# Titan_v1p6.net
KiCad netlist of a schematic drawn in EAGLE
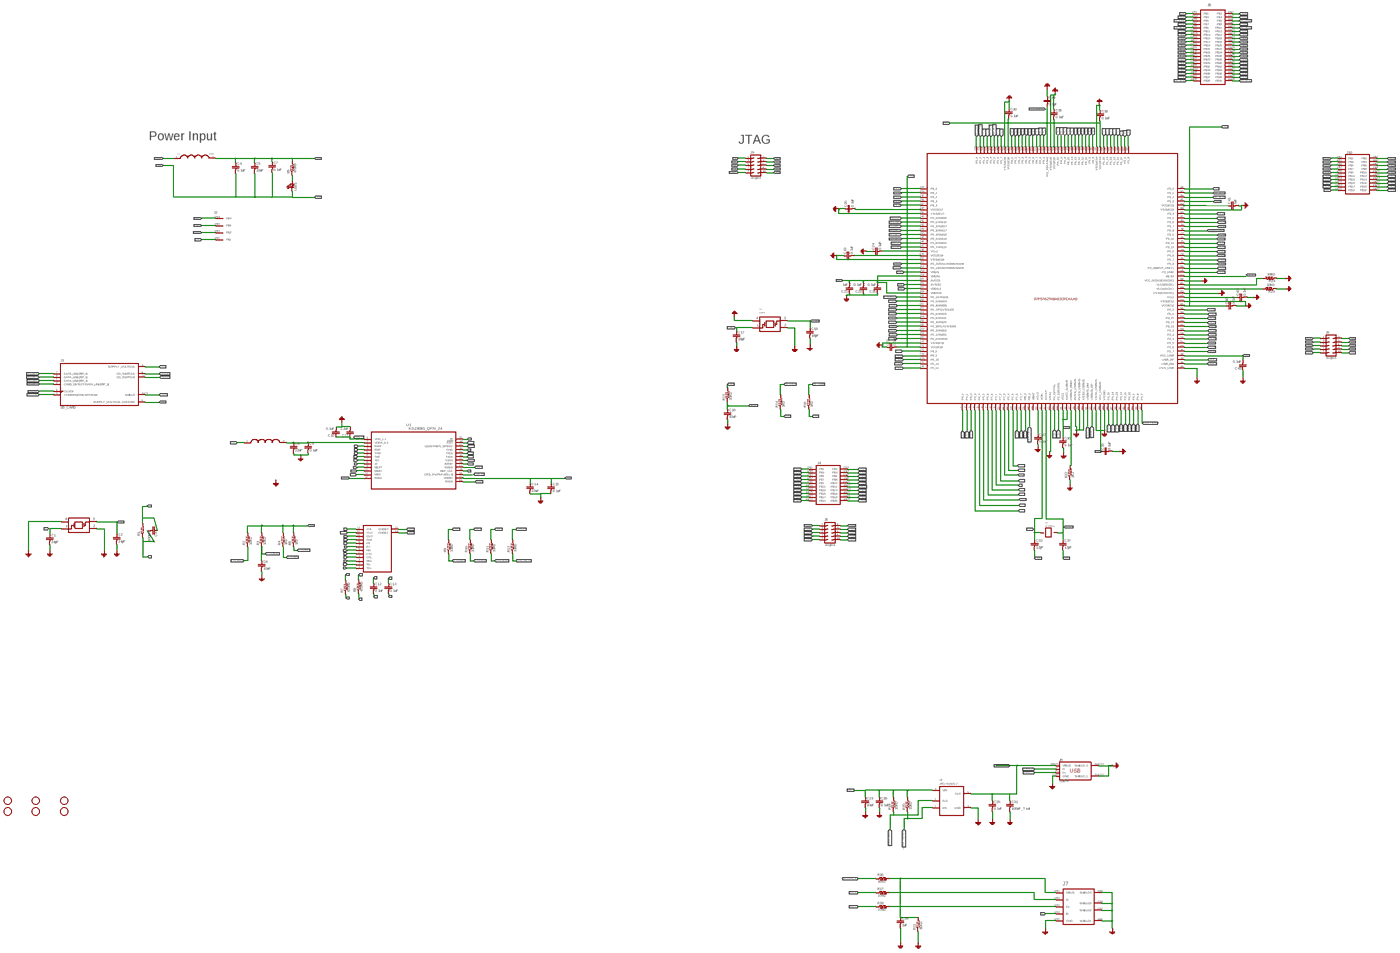
[diagram p0: schematic, sheet 1, overview]
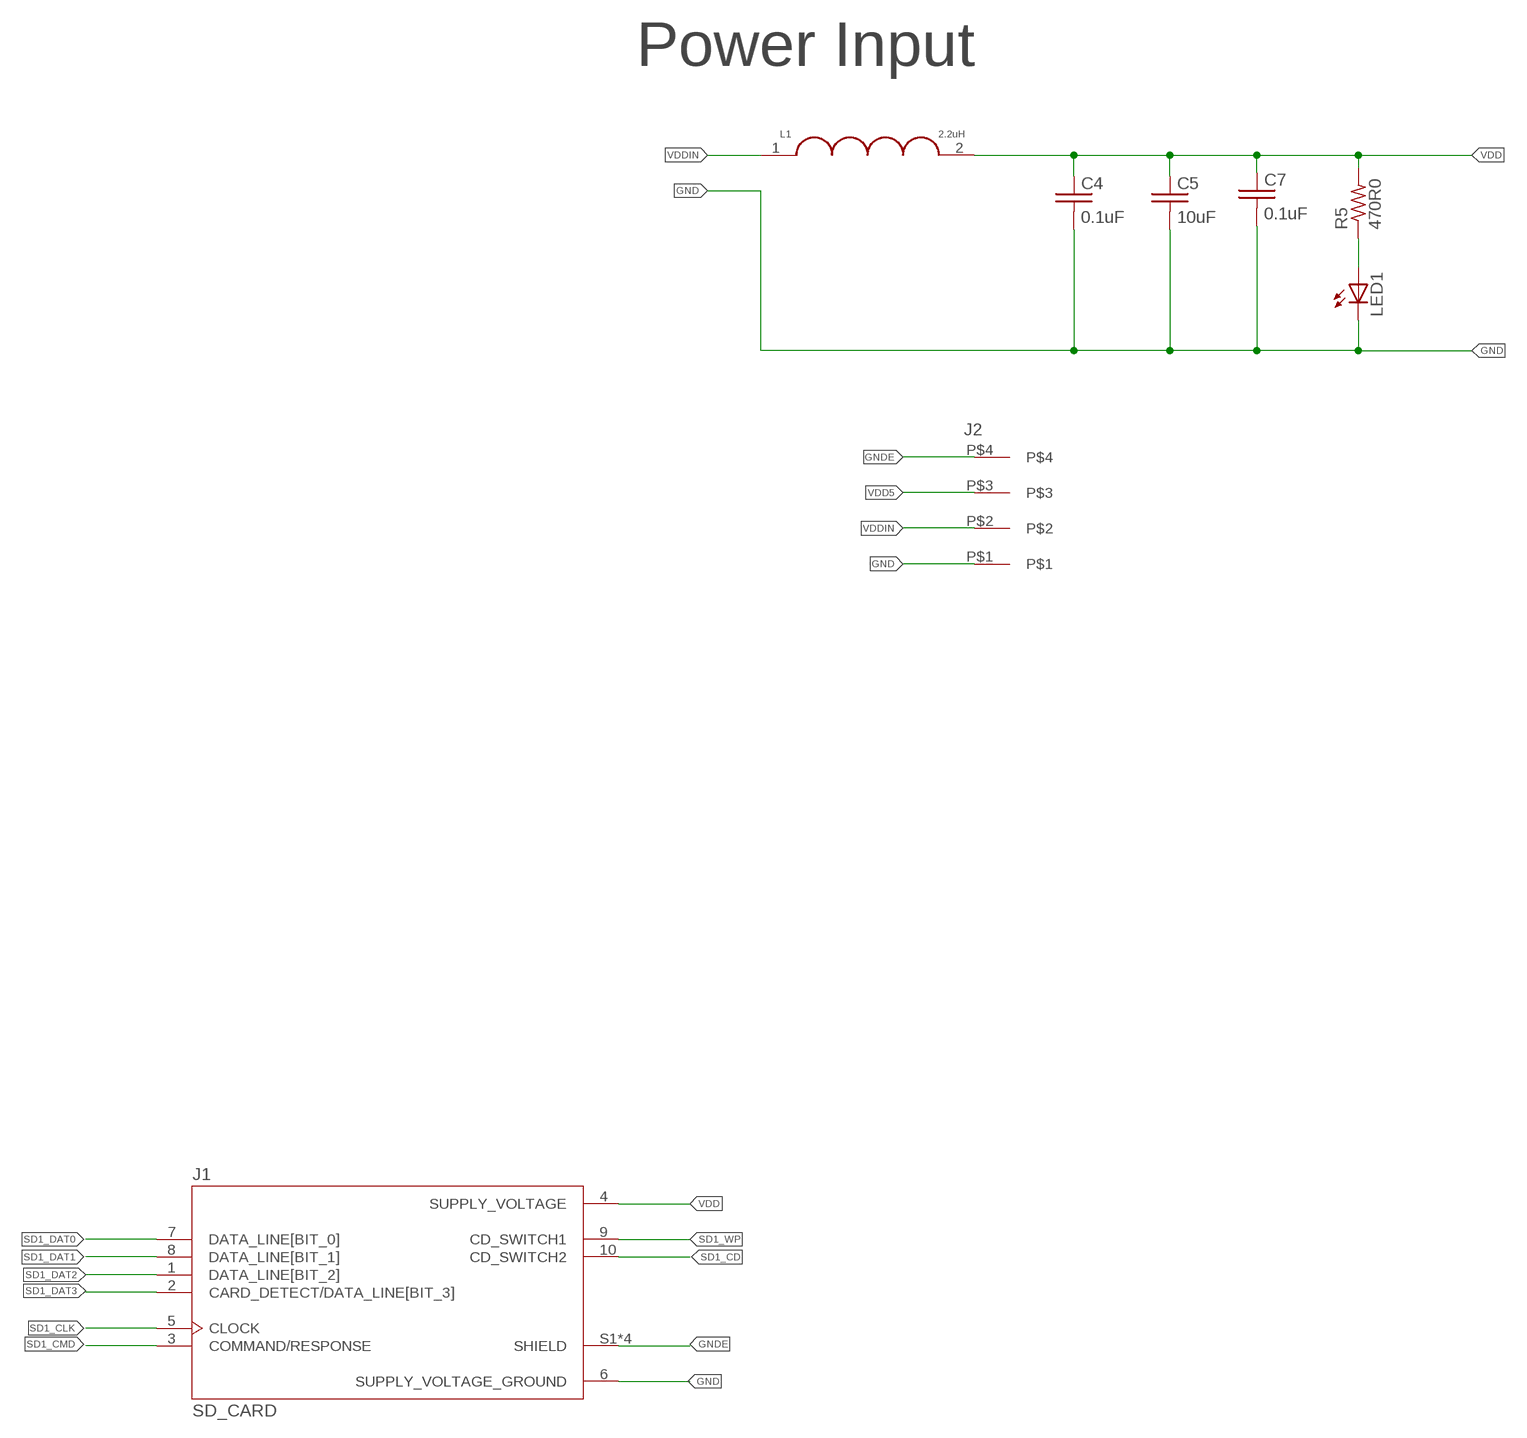
[diagram p1: schematic, sheet 1, part 1 of 5]
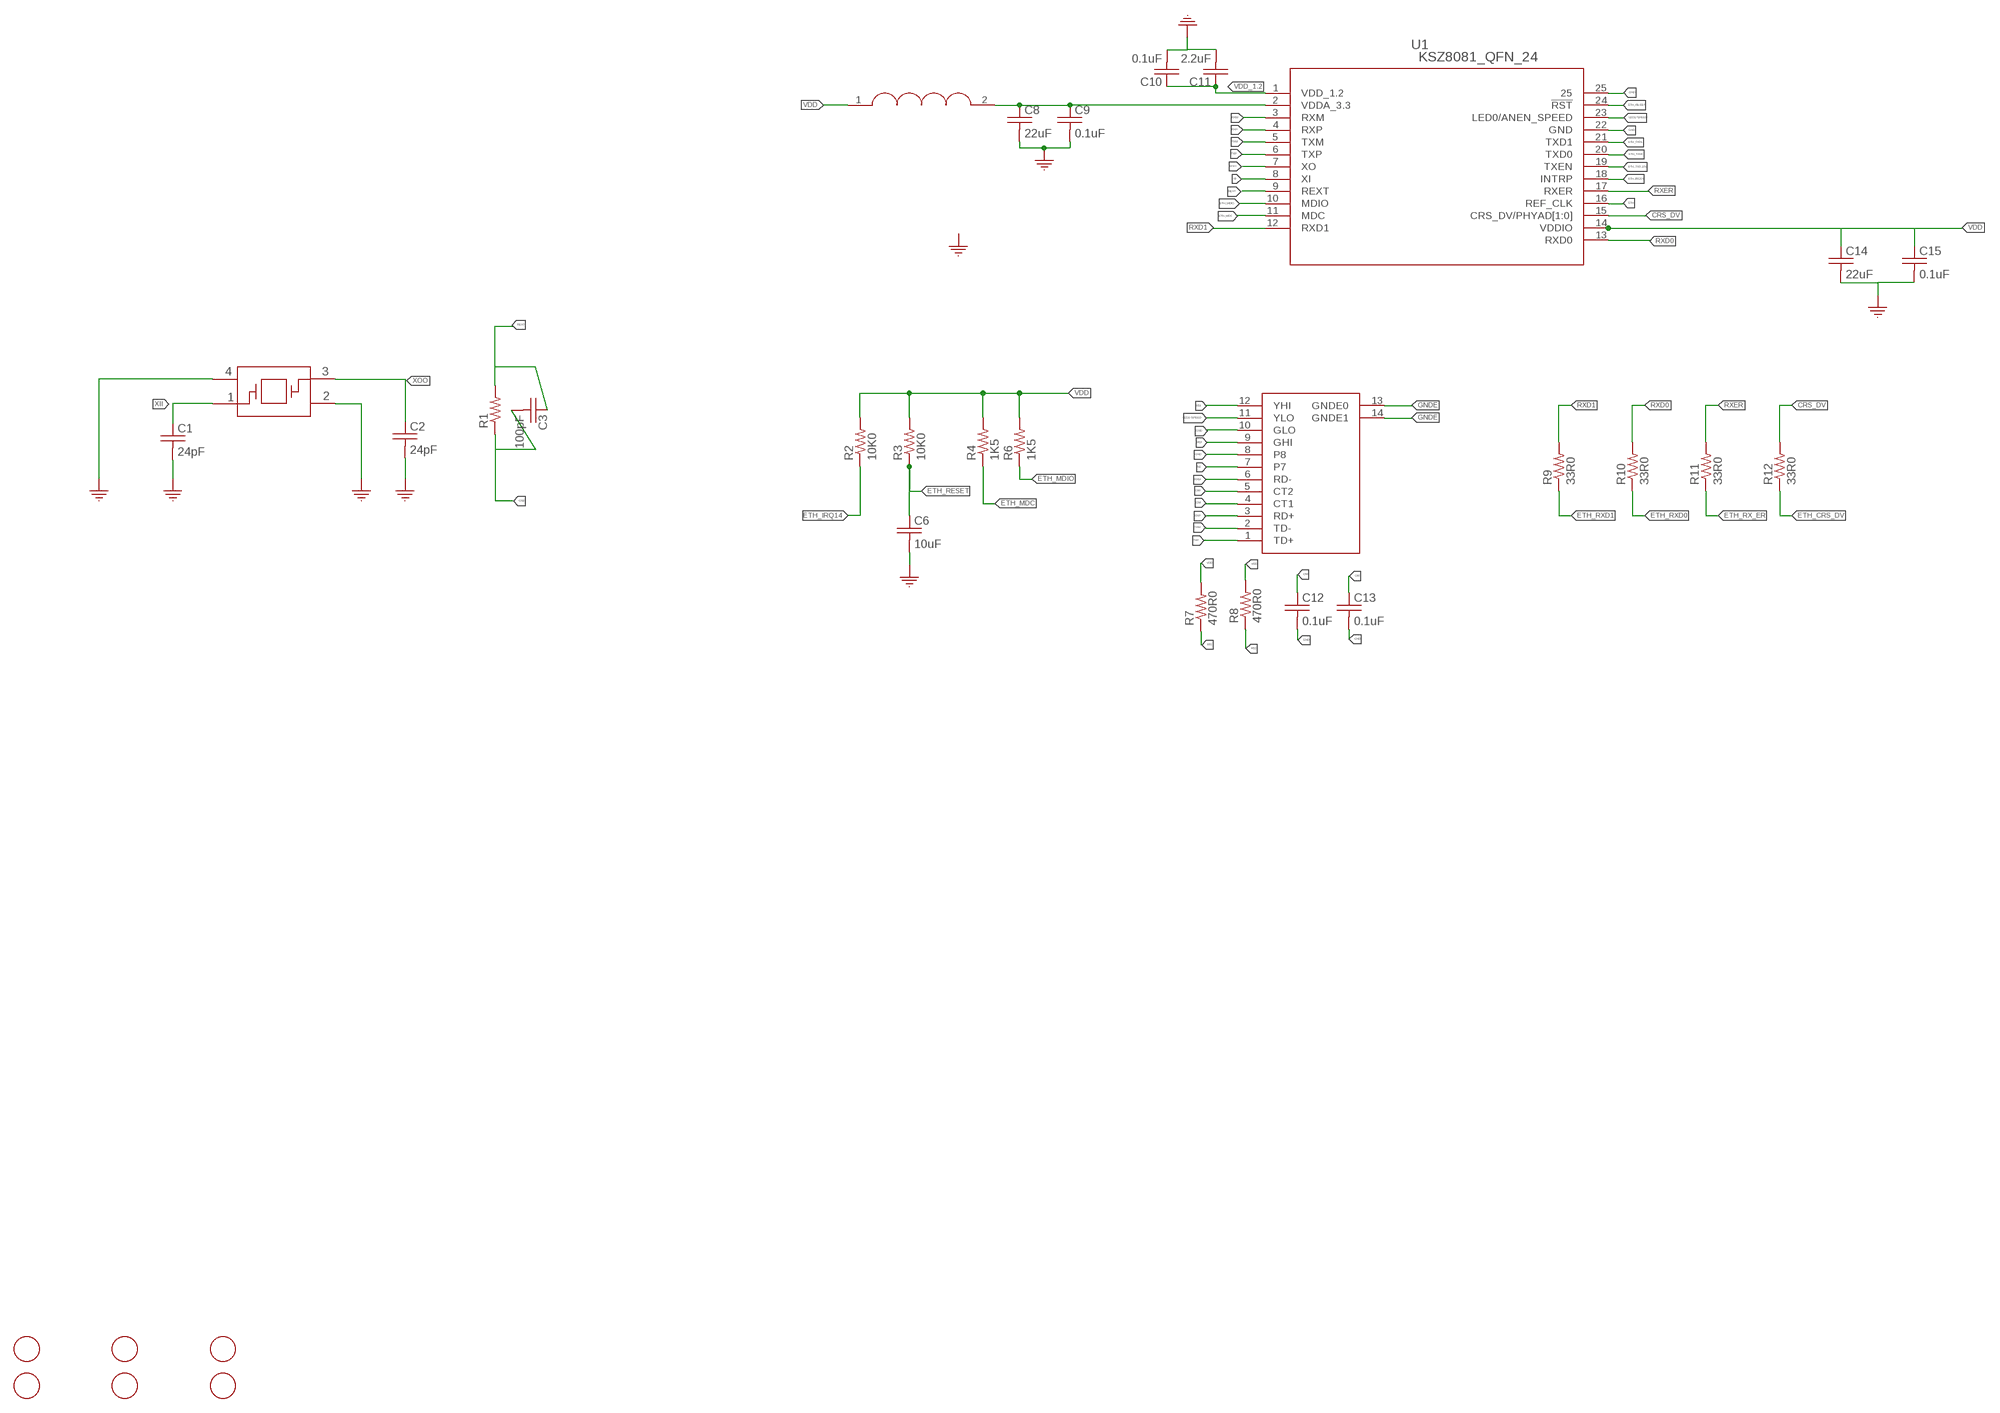
[diagram p2: schematic, sheet 1, part 2 of 5]
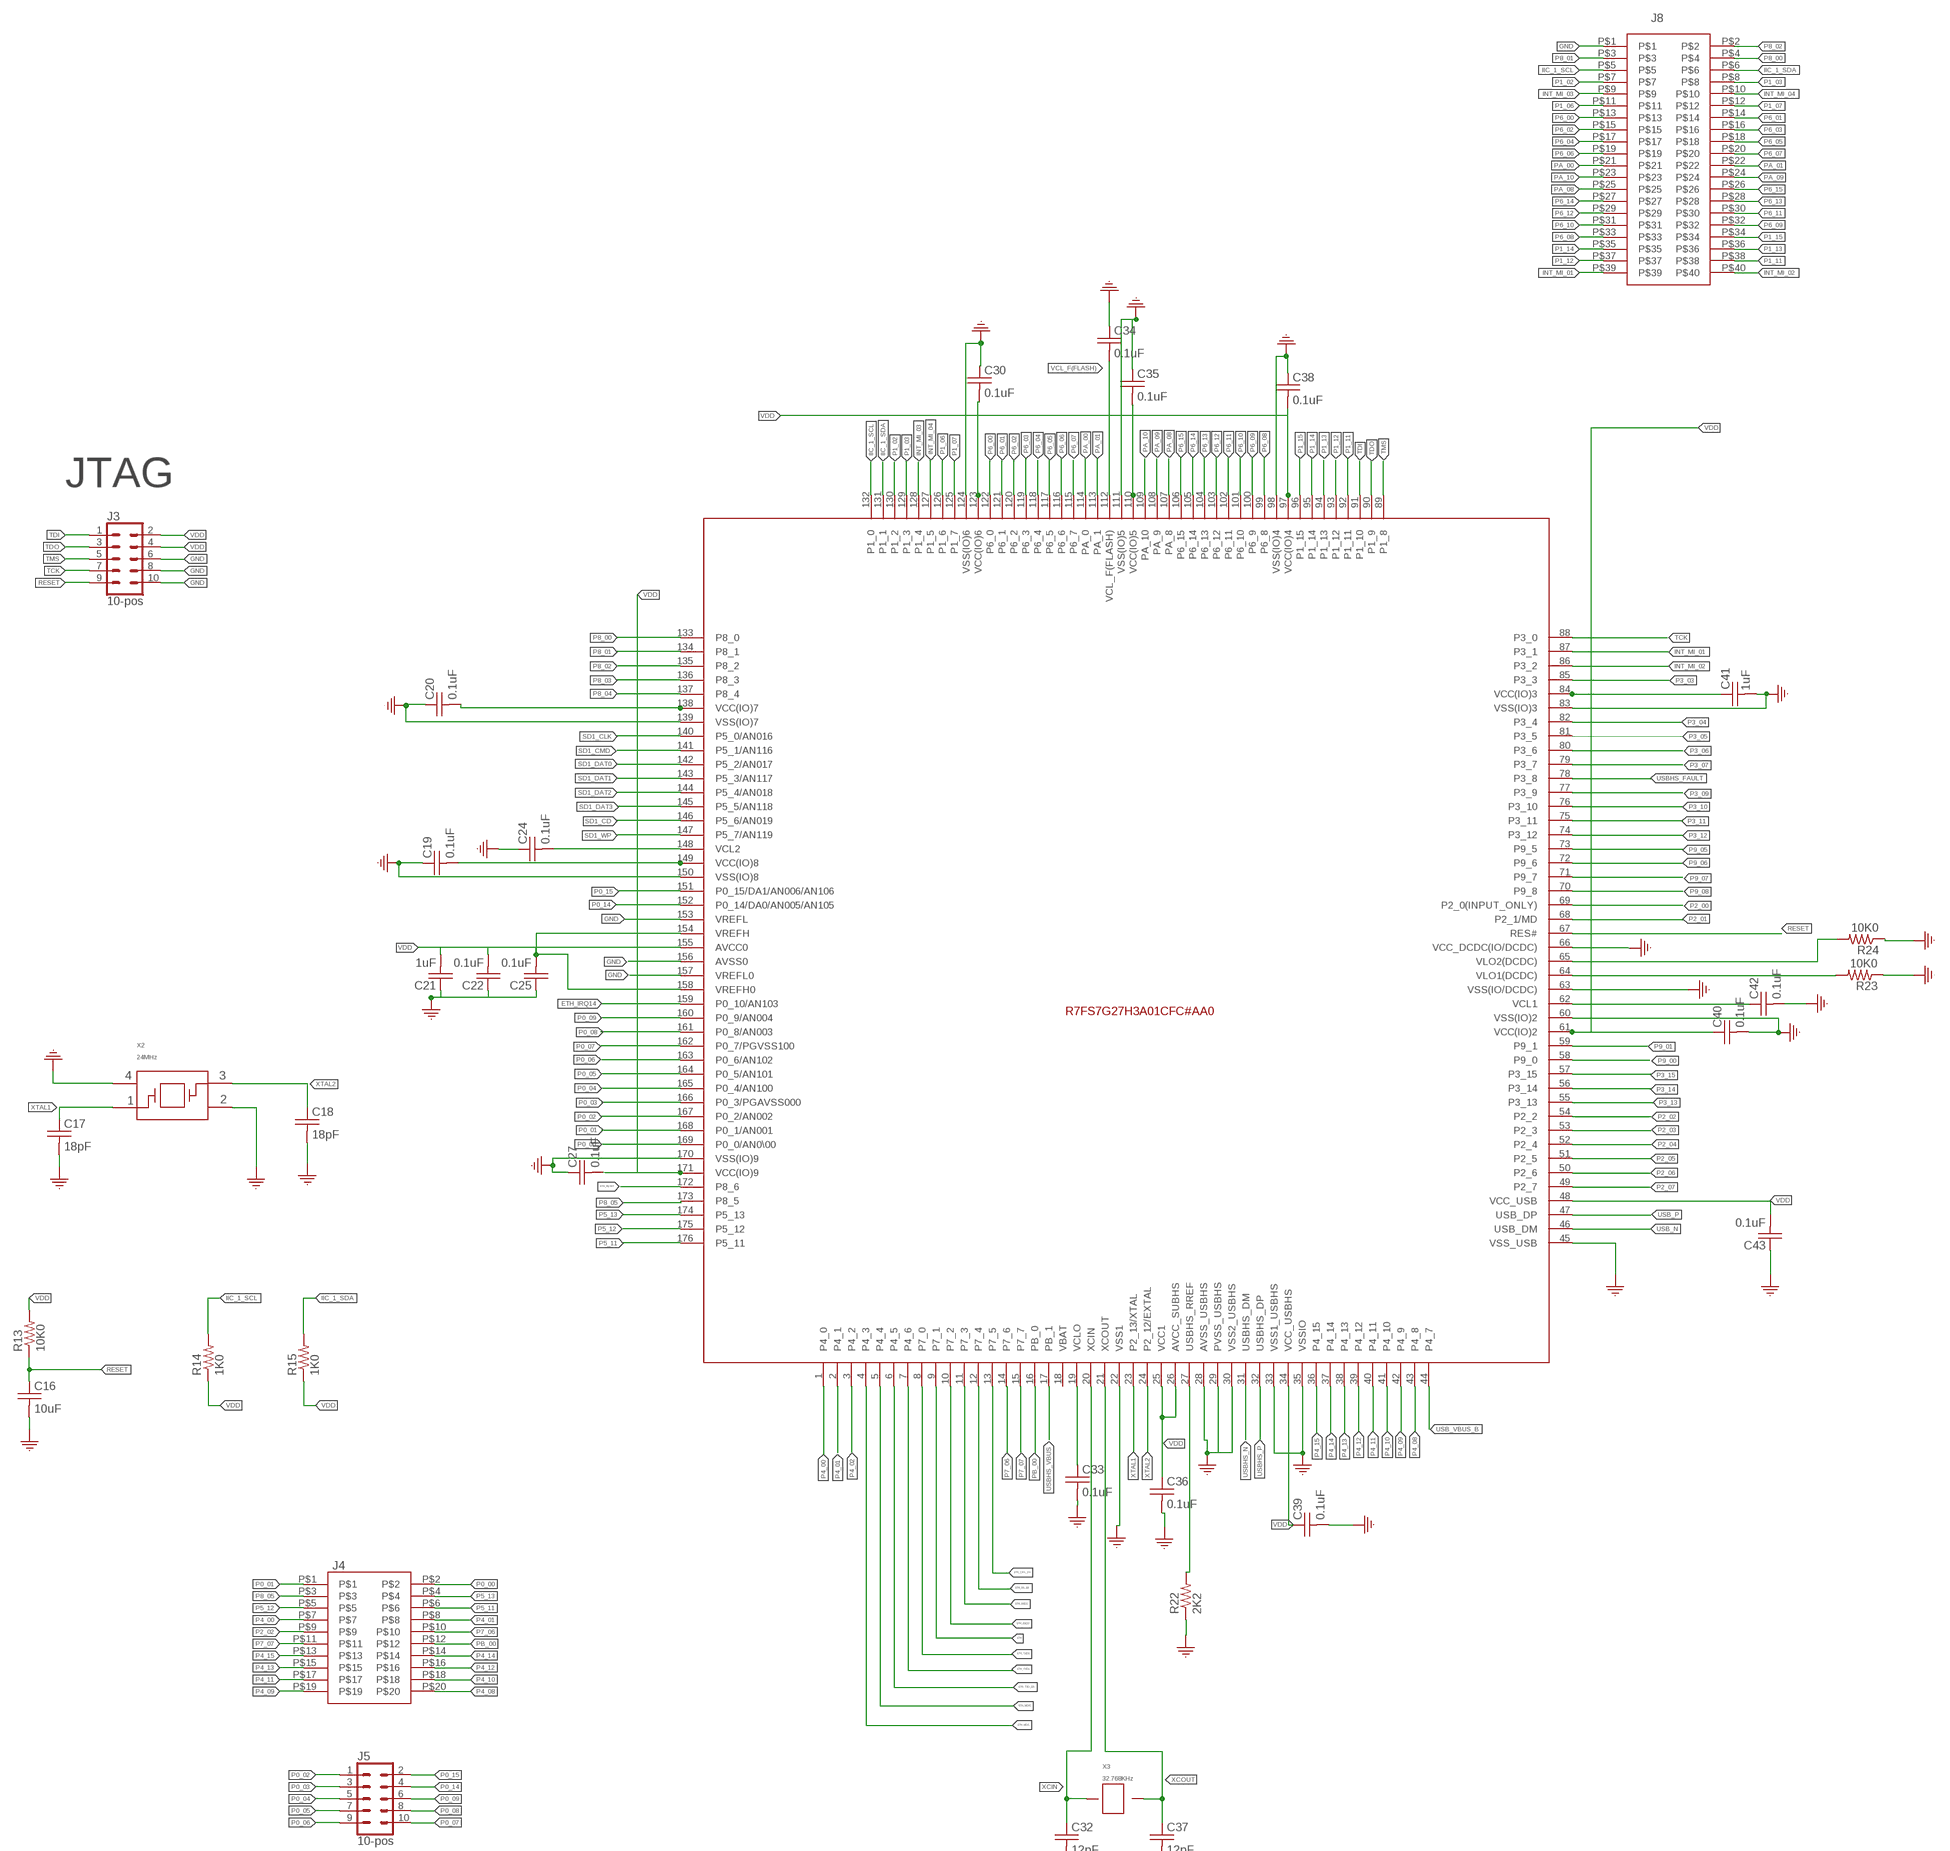
[diagram p3: schematic, sheet 1, part 3 of 5]
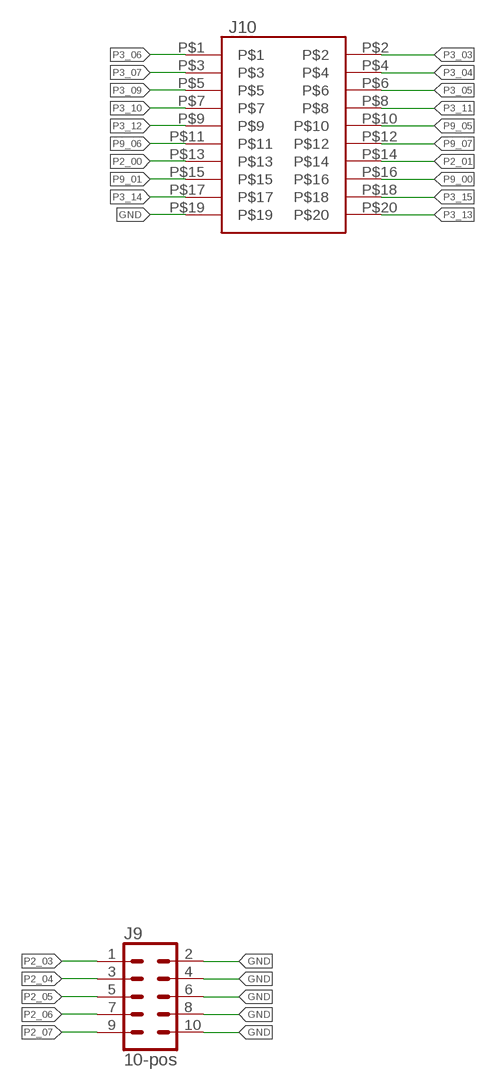
[diagram p4: schematic, sheet 1, part 4 of 5]
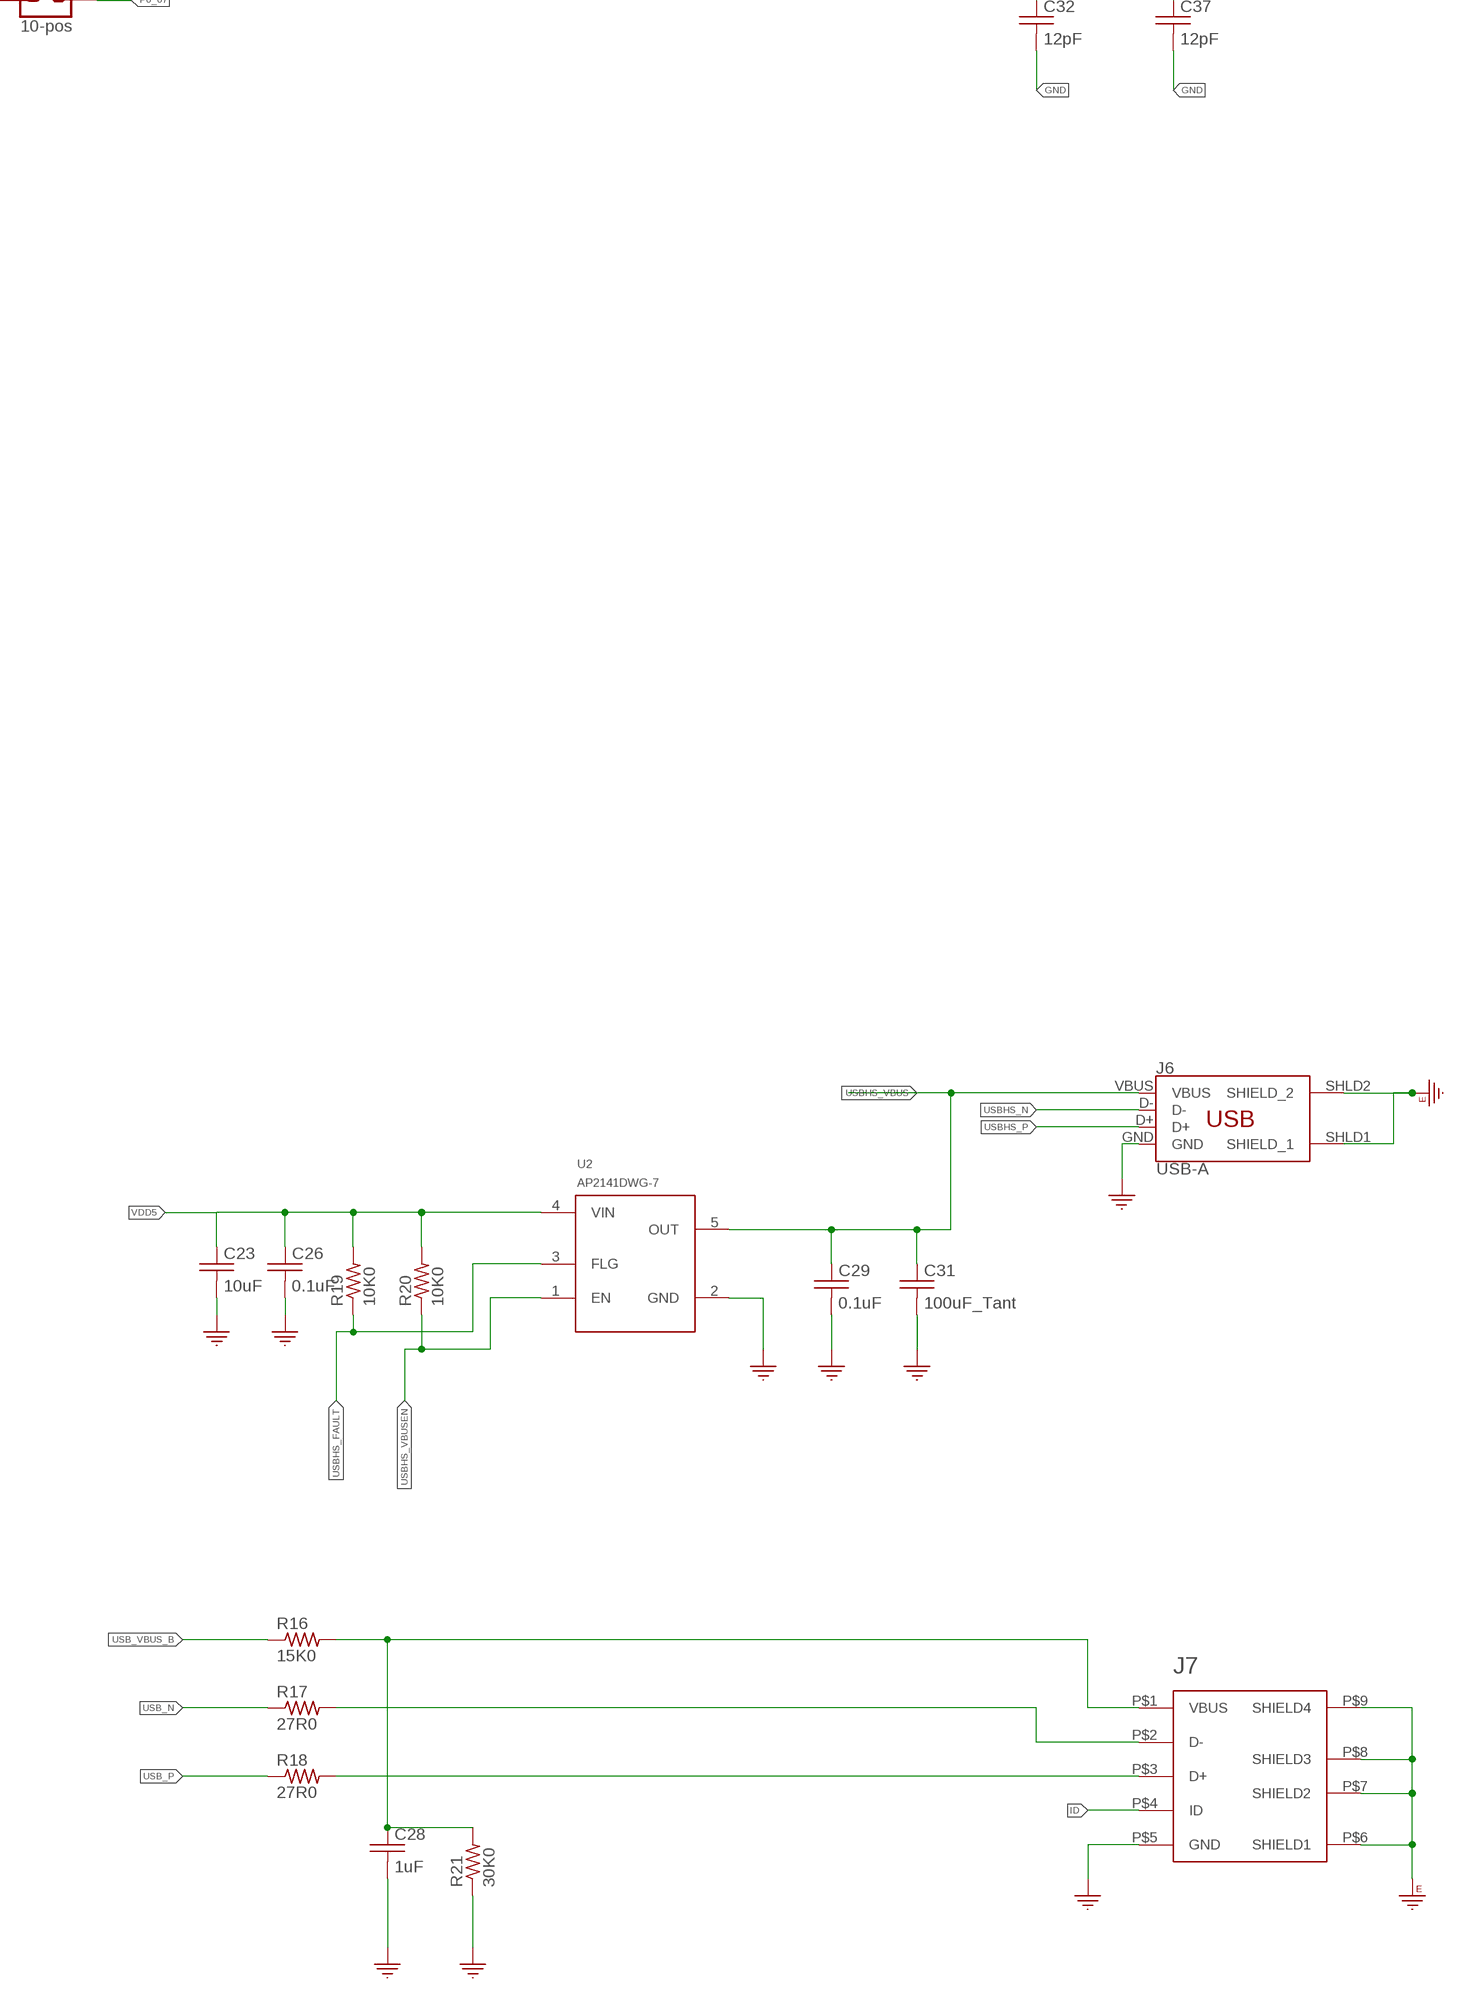
[diagram p5: schematic, sheet 1, part 5 of 5]

(export (version "E")
  (design (tool "Eeschema 10.0.6"))
  (components
    (comp (ref "AFID1")
      (value "FIDUCIAL_1MM")
      (footprint "eagle-import:FIDUCIAL_1MM")
      (libsource (lib "eagle-import") (part "FIDUCIAL_1MM"))
    )
    (comp (ref "AFID2")
      (value "FIDUCIAL_1MM")
      (footprint "eagle-import:FIDUCIAL_1MM")
      (libsource (lib "eagle-import") (part "FIDUCIAL_1MM"))
    )
    (comp (ref "AFID3")
      (value "FIDUCIAL_1MM")
      (footprint "eagle-import:FIDUCIAL_1MM")
      (libsource (lib "eagle-import") (part "FIDUCIAL_1MM"))
    )
    (comp (ref "AFID4")
      (value "FIDUCIAL_1MM")
      (footprint "eagle-import:FIDUCIAL_1MM")
      (libsource (lib "eagle-import") (part "FIDUCIAL_1MM"))
    )
    (comp (ref "AFID5")
      (value "FIDUCIAL_1MM")
      (footprint "eagle-import:FIDUCIAL_1MM")
      (libsource (lib "eagle-import") (part "FIDUCIAL_1MM"))
    )
    (comp (ref "AFID6")
      (value "FIDUCIAL_1MM")
      (footprint "eagle-import:FIDUCIAL_1MM")
      (libsource (lib "eagle-import") (part "FIDUCIAL_1MM"))
    )
    (comp (ref "C1")
      (value "24pF")
      (footprint "eagle-import:0402")
      (fields (field (name "PARTNO") "CC0402GRNPO9BN240"))
      (libsource (lib "eagle-import") (part "C_0402_24PF"))
    )
    (comp (ref "C2")
      (value "24pF")
      (footprint "eagle-import:0402")
      (fields (field (name "PARTNO") "CC0402GRNPO9BN240"))
      (libsource (lib "eagle-import") (part "C_0402_24PF"))
    )
    (comp (ref "C3")
      (value "100pF")
      (footprint "eagle-import:0402")
      (fields (field (name "PARTNO") "CL05C101JB5NNNC"))
      (libsource (lib "eagle-import") (part "C_0402_100PF"))
    )
    (comp (ref "C4")
      (value "0.1uF")
      (footprint "eagle-import:0402")
      (fields (field (name "PARTNO") "CL05F104ZO5NNNC"))
      (libsource (lib "eagle-import") (part "C_0402_0.1UF"))
    )
    (comp (ref "C5")
      (value "10uF")
      (footprint "eagle-import:0402")
      (fields (field (name "PARTNO") "CL05A106MP8NUB8"))
      (libsource (lib "eagle-import") (part "C_0402_10UF"))
    )
    (comp (ref "C6")
      (value "10uF")
      (footprint "eagle-import:0402")
      (fields (field (name "PARTNO") "CL05A106MP8NUB8"))
      (libsource (lib "eagle-import") (part "C_0402_10UF"))
    )
    (comp (ref "C7")
      (value "0.1uF")
      (footprint "eagle-import:0402")
      (fields (field (name "PARTNO") "CL05F104ZO5NNNC"))
      (libsource (lib "eagle-import") (part "C_0402_0.1UF"))
    )
    (comp (ref "C8")
      (value "22uF")
      (footprint "eagle-import:0402")
      (fields (field (name "PARTNO") "CL05A226MQ5N6J8"))
      (libsource (lib "eagle-import") (part "C_0402_22UF"))
    )
    (comp (ref "C9")
      (value "0.1uF")
      (footprint "eagle-import:0402")
      (fields (field (name "PARTNO") "CL05F104ZO5NNNC"))
      (libsource (lib "eagle-import") (part "C_0402_0.1UF"))
    )
    (comp (ref "C10")
      (value "0.1uF")
      (footprint "eagle-import:0402")
      (fields (field (name "PARTNO") "CL05F104ZO5NNNC"))
      (libsource (lib "eagle-import") (part "C_0402_0.1UF"))
    )
    (comp (ref "C11")
      (value "2.2uF")
      (footprint "eagle-import:0402")
      (fields (field (name "PARTNO") "GRM155C81C225ME15D"))
      (libsource (lib "eagle-import") (part "C_0402_2.2UF"))
    )
    (comp (ref "C12")
      (value "0.1uF")
      (footprint "eagle-import:0402")
      (fields (field (name "PARTNO") "CL05F104ZO5NNNC"))
      (libsource (lib "eagle-import") (part "C_0402_0.1UF"))
    )
    (comp (ref "C13")
      (value "0.1uF")
      (footprint "eagle-import:0402")
      (fields (field (name "PARTNO") "CL05F104ZO5NNNC"))
      (libsource (lib "eagle-import") (part "C_0402_0.1UF"))
    )
    (comp (ref "C14")
      (value "22uF")
      (footprint "eagle-import:0402")
      (fields (field (name "PARTNO") "CL05A226MQ5N6J8"))
      (libsource (lib "eagle-import") (part "C_0402_22UF"))
    )
    (comp (ref "C15")
      (value "0.1uF")
      (footprint "eagle-import:0402")
      (fields (field (name "PARTNO") "CL05F104ZO5NNNC"))
      (libsource (lib "eagle-import") (part "C_0402_0.1UF"))
    )
    (comp (ref "C16")
      (value "10uF")
      (footprint "eagle-import:0402")
      (fields (field (name "PARTNO") "CL05A106MP8NUB8"))
      (libsource (lib "eagle-import") (part "C_0402_10UF"))
    )
    (comp (ref "C17")
      (value "18pF")
      (footprint "eagle-import:0402")
      (fields (field (name "PARTNO") "UMK105CG180JV-F"))
      (libsource (lib "eagle-import") (part "C_0402_18PF"))
    )
    (comp (ref "C18")
      (value "18pF")
      (footprint "eagle-import:0402")
      (fields (field (name "PARTNO") "UMK105CG180JV-F"))
      (libsource (lib "eagle-import") (part "C_0402_18PF"))
    )
    (comp (ref "C19")
      (value "0.1uF")
      (footprint "eagle-import:0402")
      (fields (field (name "PARTNO") "CL05F104ZO5NNNC"))
      (libsource (lib "eagle-import") (part "C_0402_0.1UF"))
    )
    (comp (ref "C20")
      (value "0.1uF")
      (footprint "eagle-import:0402")
      (fields (field (name "PARTNO") "CL05F104ZO5NNNC"))
      (libsource (lib "eagle-import") (part "C_0402_0.1UF"))
    )
    (comp (ref "C21")
      (value "1uF")
      (footprint "eagle-import:0402")
      (fields (field (name "PARTNO") "CL05A105KO5NNNC"))
      (libsource (lib "eagle-import") (part "C_0402_1UF"))
    )
    (comp (ref "C22")
      (value "0.1uF")
      (footprint "eagle-import:0402")
      (fields (field (name "PARTNO") "CL05F104ZO5NNNC"))
      (libsource (lib "eagle-import") (part "C_0402_0.1UF"))
    )
    (comp (ref "C23")
      (value "10uF")
      (footprint "eagle-import:0402")
      (fields (field (name "PARTNO") "CL05A106MP8NUB8"))
      (libsource (lib "eagle-import") (part "C_0402_10UF"))
    )
    (comp (ref "C24")
      (value "0.1uF")
      (footprint "eagle-import:0402")
      (fields (field (name "PARTNO") "CL05F104ZO5NNNC"))
      (libsource (lib "eagle-import") (part "C_0402_0.1UF"))
    )
    (comp (ref "C25")
      (value "0.1uF")
      (footprint "eagle-import:0402")
      (fields (field (name "PARTNO") "CL05F104ZO5NNNC"))
      (libsource (lib "eagle-import") (part "C_0402_0.1UF"))
    )
    (comp (ref "C26")
      (value "0.1uF")
      (footprint "eagle-import:0402")
      (fields (field (name "PARTNO") "CL05F104ZO5NNNC"))
      (libsource (lib "eagle-import") (part "C_0402_0.1UF"))
    )
    (comp (ref "C27")
      (value "0.1uF")
      (footprint "eagle-import:0402")
      (fields (field (name "PARTNO") "CL05F104ZO5NNNC"))
      (libsource (lib "eagle-import") (part "C_0402_0.1UF"))
    )
    (comp (ref "C28")
      (value "1uF")
      (footprint "eagle-import:0402")
      (fields (field (name "PARTNO") "CL05A105KO5NNNC"))
      (libsource (lib "eagle-import") (part "C_0402_1UF"))
    )
    (comp (ref "C29")
      (value "0.1uF")
      (footprint "eagle-import:0402")
      (fields (field (name "PARTNO") "CL05F104ZO5NNNC"))
      (libsource (lib "eagle-import") (part "C_0402_0.1UF"))
    )
    (comp (ref "C30")
      (value "0.1uF")
      (footprint "eagle-import:0402")
      (fields (field (name "PARTNO") "CL05F104ZO5NNNC"))
      (libsource (lib "eagle-import") (part "C_0402_0.1UF"))
    )
    (comp (ref "C31")
      (value "100uF_Tant")
      (footprint "eagle-import:C1210")
      (fields (field (name "PARTNO") "TLJT107M010R0900"))
      (libsource (lib "eagle-import") (part "C_1210_100UF_TANT"))
    )
    (comp (ref "C32")
      (value "12pF")
      (footprint "eagle-import:0402")
      (fields (field (name "PARTNO") "CL05C120JB5NNNC"))
      (libsource (lib "eagle-import") (part "C_0402_12PF"))
    )
    (comp (ref "C33")
      (value "0.1uF")
      (footprint "eagle-import:0402")
      (fields (field (name "PARTNO") "CL05F104ZO5NNNC"))
      (libsource (lib "eagle-import") (part "C_0402_0.1UF"))
    )
    (comp (ref "C34")
      (value "0.1uF")
      (footprint "eagle-import:0402")
      (fields (field (name "PARTNO") "CL05F104ZO5NNNC"))
      (libsource (lib "eagle-import") (part "C_0402_0.1UF"))
    )
    (comp (ref "C35")
      (value "0.1uF")
      (footprint "eagle-import:0402")
      (fields (field (name "PARTNO") "CL05F104ZO5NNNC"))
      (libsource (lib "eagle-import") (part "C_0402_0.1UF"))
    )
    (comp (ref "C36")
      (value "0.1uF")
      (footprint "eagle-import:0402")
      (fields (field (name "PARTNO") "CL05F104ZO5NNNC"))
      (libsource (lib "eagle-import") (part "C_0402_0.1UF"))
    )
    (comp (ref "C37")
      (value "12pF")
      (footprint "eagle-import:0402")
      (fields (field (name "PARTNO") "CL05C120JB5NNNC"))
      (libsource (lib "eagle-import") (part "C_0402_12PF"))
    )
    (comp (ref "C38")
      (value "0.1uF")
      (footprint "eagle-import:0402")
      (fields (field (name "PARTNO") "CL05F104ZO5NNNC"))
      (libsource (lib "eagle-import") (part "C_0402_0.1UF"))
    )
    (comp (ref "C39")
      (value "0.1uF")
      (footprint "eagle-import:0402")
      (fields (field (name "PARTNO") "CL05F104ZO5NNNC"))
      (libsource (lib "eagle-import") (part "C_0402_0.1UF"))
    )
    (comp (ref "C40")
      (value "0.1uF")
      (footprint "eagle-import:0402")
      (fields (field (name "PARTNO") "CL05F104ZO5NNNC"))
      (libsource (lib "eagle-import") (part "C_0402_0.1UF"))
    )
    (comp (ref "C41")
      (value "1uF")
      (footprint "eagle-import:0402")
      (fields (field (name "PARTNO") "CL05A105KO5NNNC"))
      (libsource (lib "eagle-import") (part "C_0402_1UF"))
    )
    (comp (ref "C42")
      (value "0.1uF")
      (footprint "eagle-import:0402")
      (fields (field (name "PARTNO") "CL05F104ZO5NNNC"))
      (libsource (lib "eagle-import") (part "C_0402_0.1UF"))
    )
    (comp (ref "C43")
      (value "0.1uF")
      (footprint "eagle-import:0402")
      (fields (field (name "PARTNO") "CL05F104ZO5NNNC"))
      (libsource (lib "eagle-import") (part "C_0402_0.1UF"))
    )
    (comp (ref "FB1")
      (value "FB2_603")
      (footprint "eagle-import:0603")
      (fields (field (name "PARTNO") "BLM18PG121SN1D"))
      (libsource (lib "eagle-import") (part "FB_0603_120_OHM0603"))
    )
    (comp (ref "J1")
      (value "SD_CARD")
      (footprint "eagle-import:SD_CARD")
      (fields (field (name "MF") "Amphenol ICC") (field (name "PARTNO") "114-00841-68"))
      (libsource (lib "eagle-import") (part "SD_CARD_1140084168"))
    )
    (comp (ref "J2")
      (value "4-pos")
      (footprint "eagle-import:1X4_3.81MM_PITCH")
      (fields (field (name "PARTNO") "691322310004"))
      (libsource (lib "eagle-import") (part "3.81MM_1_X_4_RT_ANGLE_PLUG_HEADER"))
    )
    (comp (ref "J3")
      (value "10-pos")
      (footprint "eagle-import:2X5")
      (fields (field (name "PARTNO") "PH2RA-10-UA"))
      (libsource (lib "eagle-import") (part "CONN_05X2_RAPTH"))
    )
    (comp (ref "J4")
      (value "20-pos")
      (footprint "eagle-import:2_X_10_.1_INCH")
      (fields (field (name "PARTNO") "67996-420HLF"))
      (libsource (lib "eagle-import") (part "2_X_10_HEADER_GENERIC"))
    )
    (comp (ref "J5")
      (value "10-pos")
      (footprint "eagle-import:2X5")
      (fields (field (name "PARTNO") "PH2RA-10-UA"))
      (libsource (lib "eagle-import") (part "CONN_05X2_RAPTH"))
    )
    (comp (ref "J6")
      (value "USB-A")
      (footprint "eagle-import:USB_A_SMT")
      (fields (field (name "PARTNO") "87583-3010RPALF"))
      (libsource (lib "eagle-import") (part "USB_A"))
    )
    (comp (ref "J7")
      (value "USB-B-Micro")
      (footprint "eagle-import:USB_MICRO-B")
      (fields (field (name "PARTNO") "10118192-0002LF"))
      (libsource (lib "eagle-import") (part "USB_MICRO-B"))
    )
    (comp (ref "J8")
      (value "40-pos")
      (footprint "eagle-import:HEADER_2_X_20_.1_INCH")
      (fields (field (name "PARTNO") "61304021021"))
      (libsource (lib "eagle-import") (part "HEADER_2_X_20_GENERIC"))
    )
    (comp (ref "J9")
      (value "10-pos")
      (footprint "eagle-import:2X5")
      (fields (field (name "PARTNO") "PH2RA-10-UA"))
      (libsource (lib "eagle-import") (part "CONN_05X2_RAPTH"))
    )
    (comp (ref "J10")
      (value "20-pos")
      (footprint "eagle-import:2_X_10_.1_INCH")
      (fields (field (name "PARTNO") "67996-420HLF"))
      (libsource (lib "eagle-import") (part "2_X_10_HEADER_GENERIC"))
    )
    (comp (ref "L1")
      (value "2.2uH")
      (footprint "eagle-import:1008")
      (fields (field (name "PARTNO") "LQM2HPN2R2MG0L"))
      (libsource (lib "eagle-import") (part "INDUCTOR_1008_2.2_MH_1.3A"))
    )
    (comp (ref "LED1")
      (value "Green")
      (footprint "eagle-import:0805")
      (fields (field (name "PARTNO") "LG R971-KN-1"))
      (libsource (lib "eagle-import") (part "LED_0805_GREEN"))
    )
    (comp (ref "R1")
      (value "6K49")
      (footprint "eagle-import:0402")
      (fields (field (name "PARTNO") "RMCF0402FT6K49"))
      (libsource (lib "eagle-import") (part "R_0402_6K49"))
    )
    (comp (ref "R2")
      (value "10K0")
      (footprint "eagle-import:0402")
      (fields (field (name "PARTNO") "RMCF0402JT10K0"))
      (libsource (lib "eagle-import") (part "R_0402_10K0"))
    )
    (comp (ref "R3")
      (value "10K0")
      (footprint "eagle-import:0402")
      (fields (field (name "PARTNO") "RMCF0402JT10K0"))
      (libsource (lib "eagle-import") (part "R_0402_10K0"))
    )
    (comp (ref "R4")
      (value "1K5")
      (footprint "eagle-import:0402")
      (fields (field (name "PARTNO") "RMCF0402JT1K50"))
      (libsource (lib "eagle-import") (part "R_0402_1K5"))
    )
    (comp (ref "R5")
      (value "470R0")
      (footprint "eagle-import:0402")
      (fields (field (name "PARTNO") "RMCF0402JT470R"))
      (libsource (lib "eagle-import") (part "R_0402_470R0"))
    )
    (comp (ref "R6")
      (value "1K5")
      (footprint "eagle-import:0402")
      (fields (field (name "PARTNO") "RMCF0402JT1K50"))
      (libsource (lib "eagle-import") (part "R_0402_1K5"))
    )
    (comp (ref "R7")
      (value "470R0")
      (footprint "eagle-import:0402")
      (fields (field (name "PARTNO") "RMCF0402JT470R"))
      (libsource (lib "eagle-import") (part "R_0402_470R0"))
    )
    (comp (ref "R8")
      (value "470R0")
      (footprint "eagle-import:0402")
      (fields (field (name "PARTNO") "RMCF0402JT470R"))
      (libsource (lib "eagle-import") (part "R_0402_470R0"))
    )
    (comp (ref "R9")
      (value "33R0")
      (footprint "eagle-import:0402")
      (fields (field (name "PARTNO") "RMCF0402JT33R0"))
      (libsource (lib "eagle-import") (part "R_0402_33R0"))
    )
    (comp (ref "R10")
      (value "33R0")
      (footprint "eagle-import:0402")
      (fields (field (name "PARTNO") "RMCF0402JT33R0"))
      (libsource (lib "eagle-import") (part "R_0402_33R0"))
    )
    (comp (ref "R11")
      (value "33R0")
      (footprint "eagle-import:0402")
      (fields (field (name "PARTNO") "RMCF0402JT33R0"))
      (libsource (lib "eagle-import") (part "R_0402_33R0"))
    )
    (comp (ref "R12")
      (value "33R0")
      (footprint "eagle-import:0402")
      (fields (field (name "PARTNO") "RMCF0402JT33R0"))
      (libsource (lib "eagle-import") (part "R_0402_33R0"))
    )
    (comp (ref "R13")
      (value "10K0")
      (footprint "eagle-import:0402")
      (fields (field (name "PARTNO") "RMCF0402JT10K0"))
      (libsource (lib "eagle-import") (part "R_0402_10K0"))
    )
    (comp (ref "R14")
      (value "1K0")
      (footprint "eagle-import:0402")
      (fields (field (name "PARTNO") "CRG0402J1K0"))
      (libsource (lib "eagle-import") (part "R_0402_1K0"))
    )
    (comp (ref "R15")
      (value "1K0")
      (footprint "eagle-import:0402")
      (fields (field (name "PARTNO") "CRG0402J1K0"))
      (libsource (lib "eagle-import") (part "R_0402_1K0"))
    )
    (comp (ref "R16")
      (value "15K0")
      (footprint "eagle-import:0402")
      (fields (field (name "PARTNO") "RMCF0402JT15K0"))
      (libsource (lib "eagle-import") (part "R_0402_15K0"))
    )
    (comp (ref "R17")
      (value "27R0")
      (footprint "eagle-import:0402")
      (fields (field (name "PARTNO") "RMCF0402JT27R0"))
      (libsource (lib "eagle-import") (part "R_0402_27R0"))
    )
    (comp (ref "R18")
      (value "27R0")
      (footprint "eagle-import:0402")
      (fields (field (name "PARTNO") "RMCF0402JT27R0"))
      (libsource (lib "eagle-import") (part "R_0402_27R0"))
    )
    (comp (ref "R19")
      (value "10K0")
      (footprint "eagle-import:0402")
      (fields (field (name "PARTNO") "RMCF0402JT10K0"))
      (libsource (lib "eagle-import") (part "R_0402_10K0"))
    )
    (comp (ref "R20")
      (value "10K0")
      (footprint "eagle-import:0402")
      (fields (field (name "PARTNO") "RMCF0402JT10K0"))
      (libsource (lib "eagle-import") (part "R_0402_10K0"))
    )
    (comp (ref "R21")
      (value "30K0")
      (footprint "eagle-import:0402")
      (fields (field (name "PARTNO") "RC0402JR-0730KL"))
      (libsource (lib "eagle-import") (part "R_0402_30K0"))
    )
    (comp (ref "R22")
      (value "2K2")
      (footprint "eagle-import:0402")
      (fields (field (name "PARTNO") "RMCF0402JT2K20"))
      (libsource (lib "eagle-import") (part "R_0402_2K2"))
    )
    (comp (ref "R23")
      (value "10K0")
      (footprint "eagle-import:0402")
      (fields (field (name "PARTNO") "RMCF0402JT10K0"))
      (libsource (lib "eagle-import") (part "R_0402_10K0"))
    )
    (comp (ref "R24")
      (value "10K0")
      (footprint "eagle-import:0402")
      (fields (field (name "PARTNO") "RMCF0402JT10K0"))
      (libsource (lib "eagle-import") (part "R_0402_10K0"))
    )
    (comp (ref "RJ1")
      (value "RJ45")
      (footprint "eagle-import:RJ45_TH_ELEC")
      (fields (field (name "PARTNO") "13F-64GYD2PL2NL"))
      (libsource (lib "eagle-import") (part "RJ45_WITH_ELEC"))
    )
    (comp (ref "U1")
      (value "KSZ8081_QFN_24")
      (footprint "eagle-import:QFN-24-M")
      (fields (field (name "PARTNO") "KSZ8081RNACA"))
      (libsource (lib "eagle-import") (part "KSZ8081RNACAQFN-24-M"))
    )
    (comp (ref "U2")
      (value "AP2151DWG-7")
      (footprint "eagle-import:SOT-23-5")
      (fields (field (name "PARTNO") "AP2151WG-7"))
      (libsource (lib "eagle-import") (part "AP2151DWG-7"))
    )
    (comp (ref "U3")
      (value "S7G2LQFP176")
      (footprint "eagle-import:LQFP176_24X24")
      (fields (field (name "PARTNO") "R7FS7G27H3A01CFC#AA0"))
      (libsource (lib "eagle-import") (part "RENESAS_S7G2_X_176"))
    )
    (comp (ref "X1")
      (value "25MHz")
      (footprint "eagle-import:SMD_3225")
      (fields (field (name "PARTNO") "FA-238 25.0000MB-B3"))
      (libsource (lib "eagle-import") (part "XTAL_25_MHZ"))
    )
    (comp (ref "X2")
      (value "24MHz")
      (footprint "eagle-import:SMD_3225")
      (fields (field (name "PARTNO") "FA-238 24.0000MB-C3 "))
      (libsource (lib "eagle-import") (part "XTAL_24_MHZ"))
    )
    (comp (ref "X3")
      (value "32.768KHz")
      (footprint "eagle-import:SMD_X_2_PADS")
      (fields (field (name "PARTNO") "ABS07-32.768KHZ-T"))
      (libsource (lib "eagle-import") (part "XTAL_32.768KHZ"))
    )
  )
  (nets
    (net (code "1") (name "C58") (class "Default")
      (node (ref "C12") (pin "P$1") (pinfunction "1_P$1") (pintype "passive"))
      (node (ref "RJ1") (pin "4") (pinfunction "CT1_4") (pintype "bidirectional"))
    )
    (net (code "2") (name "C60") (class "Default")
      (node (ref "C13") (pin "P$1") (pinfunction "1_P$1") (pintype "passive"))
      (node (ref "RJ1") (pin "5") (pinfunction "CT2_5") (pintype "bidirectional"))
    )
    (net (code "3") (name "CRS_DV") (class "Default")
      (node (ref "R12") (pin "P$2") (pinfunction "2_P$2") (pintype "passive"))
      (node (ref "U1") (pin "15") (pinfunction "CRS_DV/PHYAD[1:0]_15") (pintype "bidirectional"))
    )
    (net (code "4") (name "ETH") (class "Default")
      (node (ref "U1") (pin "16") (pinfunction "REF_CLK_16") (pintype "bidirectional"))
      (node (ref "U3") (pin "9") (pinfunction "P7_1_9") (pintype "bidirectional"))
    )
    (net (code "5") (name "ETH_CRS_DV") (class "Default")
      (node (ref "R12") (pin "P$1") (pinfunction "1_P$1") (pintype "passive"))
      (node (ref "U3") (pin "13") (pinfunction "P7_5_13") (pintype "bidirectional"))
    )
    (net (code "6") (name "ETH_IRQ14") (class "Default")
      (node (ref "R2") (pin "P$1") (pinfunction "1_P$1") (pintype "passive"))
      (node (ref "U1") (pin "18") (pinfunction "INTRP_18") (pintype "bidirectional"))
      (node (ref "U3") (pin "159") (pinfunction "P0_10/AN103_159") (pintype "bidirectional"))
    )
    (net (code "7") (name "ETH_MDC") (class "Default")
      (node (ref "R4") (pin "P$1") (pinfunction "1_P$1") (pintype "passive"))
      (node (ref "U1") (pin "11") (pinfunction "MDC_11") (pintype "input"))
      (node (ref "U3") (pin "4") (pinfunction "P4_3_4") (pintype "bidirectional"))
    )
    (net (code "8") (name "ETH_MDIO") (class "Default")
      (node (ref "R6") (pin "P$1") (pinfunction "1_P$1") (pintype "passive"))
      (node (ref "U1") (pin "10") (pinfunction "MDIO_10") (pintype "bidirectional"))
      (node (ref "U3") (pin "5") (pinfunction "P4_4_5") (pintype "bidirectional"))
    )
    (net (code "9") (name "ETH_RESET") (class "Default")
      (node (ref "C6") (pin "P$1") (pinfunction "1_P$1") (pintype "passive"))
      (node (ref "R3") (pin "P$1") (pinfunction "1_P$1") (pintype "passive"))
      (node (ref "U1") (pin "24") (pinfunction "~{RST}_24") (pintype "input"))
      (node (ref "U3") (pin "172") (pinfunction "P8_6_172") (pintype "bidirectional"))
    )
    (net (code "10") (name "ETH_RXD0") (class "Default")
      (node (ref "R10") (pin "P$1") (pinfunction "1_P$1") (pintype "passive"))
      (node (ref "U3") (pin "10") (pinfunction "P7_2_10") (pintype "bidirectional"))
    )
    (net (code "11") (name "ETH_RXD1") (class "Default")
      (node (ref "R9") (pin "P$1") (pinfunction "1_P$1") (pintype "passive"))
      (node (ref "U3") (pin "11") (pinfunction "P7_3_11") (pintype "bidirectional"))
    )
    (net (code "12") (name "ETH_RX_ER") (class "Default")
      (node (ref "R11") (pin "P$1") (pinfunction "1_P$1") (pintype "passive"))
      (node (ref "U3") (pin "12") (pinfunction "P7_4_12") (pintype "bidirectional"))
    )
    (net (code "13") (name "ETH_TXD0") (class "Default")
      (node (ref "U1") (pin "20") (pinfunction "TXD0_20") (pintype "input"))
      (node (ref "U3") (pin "8") (pinfunction "P7_0_8") (pintype "bidirectional"))
    )
    (net (code "14") (name "ETH_TXD1") (class "Default")
      (node (ref "U1") (pin "21") (pinfunction "TXD1_21") (pintype "bidirectional"))
      (node (ref "U3") (pin "7") (pinfunction "P4_6_7") (pintype "bidirectional"))
    )
    (net (code "15") (name "ETH_TXD_EN") (class "Default")
      (node (ref "U1") (pin "19") (pinfunction "TXEN_19") (pintype "input"))
      (node (ref "U3") (pin "6") (pinfunction "P4_5_6") (pintype "bidirectional"))
    )
    (net (code "16") (name "GND") (class "Default")
      (node (ref "C1") (pin "P$2") (pinfunction "2_P$2") (pintype "passive"))
      (node (ref "C10") (pin "P$2") (pinfunction "2_P$2") (pintype "passive"))
      (node (ref "C11") (pin "P$2") (pinfunction "2_P$2") (pintype "passive"))
      (node (ref "C12") (pin "P$2") (pinfunction "2_P$2") (pintype "passive"))
      (node (ref "C13") (pin "P$2") (pinfunction "2_P$2") (pintype "passive"))
      (node (ref "C14") (pin "P$2") (pinfunction "2_P$2") (pintype "passive"))
      (node (ref "C15") (pin "P$2") (pinfunction "2_P$2") (pintype "passive"))
      (node (ref "C16") (pin "P$2") (pinfunction "2_P$2") (pintype "passive"))
      (node (ref "C17") (pin "P$2") (pinfunction "2_P$2") (pintype "passive"))
      (node (ref "C18") (pin "P$2") (pinfunction "2_P$2") (pintype "passive"))
      (node (ref "C19") (pin "P$1") (pinfunction "1_P$1") (pintype "passive"))
      (node (ref "C2") (pin "P$2") (pinfunction "2_P$2") (pintype "passive"))
      (node (ref "C20") (pin "P$1") (pinfunction "1_P$1") (pintype "passive"))
      (node (ref "C21") (pin "P$1") (pinfunction "1_P$1") (pintype "passive"))
      (node (ref "C22") (pin "P$1") (pinfunction "1_P$1") (pintype "passive"))
      (node (ref "C23") (pin "P$2") (pinfunction "2_P$2") (pintype "passive"))
      (node (ref "C24") (pin "P$1") (pinfunction "1_P$1") (pintype "passive"))
      (node (ref "C25") (pin "P$1") (pinfunction "1_P$1") (pintype "passive"))
      (node (ref "C26") (pin "P$2") (pinfunction "2_P$2") (pintype "passive"))
      (node (ref "C27") (pin "P$1") (pinfunction "1_P$1") (pintype "passive"))
      (node (ref "C28") (pin "P$2") (pinfunction "2_P$2") (pintype "passive"))
      (node (ref "C29") (pin "P$2") (pinfunction "2_P$2") (pintype "passive"))
      (node (ref "C3") (pin "P$2") (pinfunction "2_P$2") (pintype "passive"))
      (node (ref "C30") (pin "P$1") (pinfunction "1_P$1") (pintype "passive"))
      (node (ref "C31") (pin "2") (pinfunction "2_2") (pintype "passive"))
      (node (ref "C32") (pin "P$2") (pinfunction "2_P$2") (pintype "passive"))
      (node (ref "C33") (pin "P$2") (pinfunction "2_P$2") (pintype "passive"))
      (node (ref "C34") (pin "P$1") (pinfunction "1_P$1") (pintype "passive"))
      (node (ref "C35") (pin "P$1") (pinfunction "1_P$1") (pintype "passive"))
      (node (ref "C36") (pin "P$2") (pinfunction "2_P$2") (pintype "passive"))
      (node (ref "C37") (pin "P$2") (pinfunction "2_P$2") (pintype "passive"))
      (node (ref "C38") (pin "P$1") (pinfunction "1_P$1") (pintype "passive"))
      (node (ref "C39") (pin "P$2") (pinfunction "2_P$2") (pintype "passive"))
      (node (ref "C4") (pin "P$2") (pinfunction "2_P$2") (pintype "passive"))
      (node (ref "C40") (pin "P$2") (pinfunction "2_P$2") (pintype "passive"))
      (node (ref "C41") (pin "P$2") (pinfunction "2_P$2") (pintype "passive"))
      (node (ref "C42") (pin "P$2") (pinfunction "2_P$2") (pintype "passive"))
      (node (ref "C43") (pin "P$1") (pinfunction "1_P$1") (pintype "passive"))
      (node (ref "C5") (pin "P$2") (pinfunction "2_P$2") (pintype "passive"))
      (node (ref "C6") (pin "P$2") (pinfunction "2_P$2") (pintype "passive"))
      (node (ref "C7") (pin "P$2") (pinfunction "2_P$2") (pintype "passive"))
      (node (ref "C8") (pin "P$2") (pinfunction "2_P$2") (pintype "passive"))
      (node (ref "C9") (pin "P$2") (pinfunction "2_P$2") (pintype "passive"))
      (node (ref "J1") (pin "6") (pinfunction "SUPPLY_VOLTAGE_GROUND_6") (pintype "power_in"))
      (node (ref "J10") (pin "P$19") (pinfunction "P$19_P$19") (pintype "bidirectional"))
      (node (ref "J2") (pin "P$1") (pinfunction "P$1_P$1") (pintype "bidirectional"))
      (node (ref "J3") (pin "10") (pinfunction "10_10") (pintype "passive"))
      (node (ref "J3") (pin "6") (pinfunction "6_6") (pintype "passive"))
      (node (ref "J3") (pin "8") (pinfunction "8_8") (pintype "passive"))
      (node (ref "J6") (pin "GND") (pinfunction "GND_GND") (pintype "power_in"))
      (node (ref "J7") (pin "P$5") (pinfunction "GND_P$5") (pintype "bidirectional"))
      (node (ref "J8") (pin "P$1") (pinfunction "P$1_P$1") (pintype "bidirectional"))
      (node (ref "J9") (pin "10") (pinfunction "10_10") (pintype "passive"))
      (node (ref "J9") (pin "2") (pinfunction "2_2") (pintype "passive"))
      (node (ref "J9") (pin "4") (pinfunction "4_4") (pintype "passive"))
      (node (ref "J9") (pin "6") (pinfunction "6_6") (pintype "passive"))
      (node (ref "J9") (pin "8") (pinfunction "8_8") (pintype "passive"))
      (node (ref "LED1") (pin "2") (pinfunction "C_2") (pintype "passive"))
      (node (ref "R1") (pin "P$1") (pinfunction "1_P$1") (pintype "passive"))
      (node (ref "R21") (pin "P$1") (pinfunction "1_P$1") (pintype "passive"))
      (node (ref "R22") (pin "P$1") (pinfunction "1_P$1") (pintype "passive"))
      (node (ref "R23") (pin "P$1") (pinfunction "1_P$1") (pintype "passive"))
      (node (ref "R24") (pin "P$1") (pinfunction "1_P$1") (pintype "passive"))
      (node (ref "RJ1") (pin "10") (pinfunction "GLO_10") (pintype "bidirectional"))
      (node (ref "RJ1") (pin "8") (pinfunction "P8_8") (pintype "bidirectional"))
      (node (ref "U1") (pin "22") (pinfunction "GND_22") (pintype "power_in"))
      (node (ref "U1") (pin "25") (pinfunction "25_25") (pintype "passive"))
      (node (ref "U2") (pin "2") (pinfunction "GND_2") (pintype "input"))
      (node (ref "U3") (pin "111") (pinfunction "VSS(IO)5_111") (pintype "bidirectional"))
      (node (ref "U3") (pin "124") (pinfunction "VSS(IO)6_124") (pintype "bidirectional"))
      (node (ref "U3") (pin "139") (pinfunction "VSS(IO)7_139") (pintype "bidirectional"))
      (node (ref "U3") (pin "150") (pinfunction "VSS(IO)8_150") (pintype "bidirectional"))
      (node (ref "U3") (pin "153") (pinfunction "VREFL_153") (pintype "bidirectional"))
      (node (ref "U3") (pin "156") (pinfunction "AVSS0_156") (pintype "bidirectional"))
      (node (ref "U3") (pin "157") (pinfunction "VREFL0_157") (pintype "bidirectional"))
      (node (ref "U3") (pin "170") (pinfunction "VSS(IO)9_170") (pintype "bidirectional"))
      (node (ref "U3") (pin "22") (pinfunction "VSS1_22") (pintype "bidirectional"))
      (node (ref "U3") (pin "28") (pinfunction "AVSS_USBHS_28") (pintype "bidirectional"))
      (node (ref "U3") (pin "29") (pinfunction "PVSS_USBHS_29") (pintype "bidirectional"))
      (node (ref "U3") (pin "30") (pinfunction "VSS2_USBHS_30") (pintype "bidirectional"))
      (node (ref "U3") (pin "33") (pinfunction "VSS1_USBHS_33") (pintype "bidirectional"))
      (node (ref "U3") (pin "35") (pinfunction "VSSIO_35") (pintype "bidirectional"))
      (node (ref "U3") (pin "45") (pinfunction "VSS_USB_45") (pintype "bidirectional"))
      (node (ref "U3") (pin "60") (pinfunction "VSS(IO)2_60") (pintype "bidirectional"))
      (node (ref "U3") (pin "63") (pinfunction "VSS(IO/DCDC)_63") (pintype "bidirectional"))
      (node (ref "U3") (pin "66") (pinfunction "VCC_DCDC(IO/DCDC)_66") (pintype "bidirectional"))
      (node (ref "U3") (pin "83") (pinfunction "VSS(IO)3_83") (pintype "bidirectional"))
      (node (ref "U3") (pin "98") (pinfunction "VSS(IO)4_98") (pintype "bidirectional"))
      (node (ref "X1") (pin "2") (pinfunction "2_2") (pintype "bidirectional"))
      (node (ref "X1") (pin "4") (pinfunction "4_4") (pintype "bidirectional"))
      (node (ref "X2") (pin "2") (pinfunction "2_2") (pintype "bidirectional"))
      (node (ref "X2") (pin "4") (pinfunction "4_4") (pintype "bidirectional"))
    )
    (net (code "17") (name "GNDE") (class "Default")
      (node (ref "J1") (pin "S1") (pinfunction "SHIELD_S1") (pintype "passive"))
      (node (ref "J1") (pin "S2") (pinfunction "SHIELD_S2") (pintype "passive"))
      (node (ref "J1") (pin "S3") (pinfunction "SHIELD_S3") (pintype "passive"))
      (node (ref "J1") (pin "S4") (pinfunction "SHIELD_S4") (pintype "passive"))
      (node (ref "J2") (pin "P$4") (pinfunction "P$4_P$4") (pintype "bidirectional"))
      (node (ref "J6") (pin "SHLD1") (pinfunction "SHIELD_1_SHLD1") (pintype "bidirectional"))
      (node (ref "J6") (pin "SHLD2") (pinfunction "SHIELD_2_SHLD2") (pintype "bidirectional"))
      (node (ref "J7") (pin "P$6") (pinfunction "SHIELD1_P$6") (pintype "bidirectional"))
      (node (ref "J7") (pin "P$7") (pinfunction "SHIELD2_P$7") (pintype "bidirectional"))
      (node (ref "J7") (pin "P$8") (pinfunction "SHIELD3_P$8") (pintype "bidirectional"))
      (node (ref "J7") (pin "P$9") (pinfunction "SHIELD4_P$9") (pintype "bidirectional"))
      (node (ref "RJ1") (pin "13") (pinfunction "GNDE0_13") (pintype "bidirectional"))
      (node (ref "RJ1") (pin "14") (pinfunction "GNDE1_14") (pintype "bidirectional"))
    )
    (net (code "18") (name "ID") (class "Default")
      (node (ref "J7") (pin "P$4") (pinfunction "ID_P$4") (pintype "bidirectional"))
    )
    (net (code "19") (name "IIC_1_SCL") (class "Default")
      (node (ref "J8") (pin "P$5") (pinfunction "P$5_P$5") (pintype "bidirectional"))
      (node (ref "R14") (pin "P$2") (pinfunction "2_P$2") (pintype "passive"))
      (node (ref "U3") (pin "132") (pinfunction "P1_0_132") (pintype "bidirectional"))
    )
    (net (code "20") (name "IIC_1_SDA") (class "Default")
      (node (ref "J8") (pin "P$6") (pinfunction "P$6_P$6") (pintype "bidirectional"))
      (node (ref "R15") (pin "P$2") (pinfunction "2_P$2") (pintype "passive"))
      (node (ref "U3") (pin "131") (pinfunction "P1_1_131") (pintype "bidirectional"))
    )
    (net (code "21") (name "INT_MI_01") (class "Default")
      (node (ref "J8") (pin "P$39") (pinfunction "P$39_P$39") (pintype "bidirectional"))
      (node (ref "U3") (pin "87") (pinfunction "P3_1_87") (pintype "bidirectional"))
    )
    (net (code "22") (name "INT_MI_02") (class "Default")
      (node (ref "J8") (pin "P$40") (pinfunction "P$40_P$40") (pintype "bidirectional"))
      (node (ref "U3") (pin "86") (pinfunction "P3_2_86") (pintype "bidirectional"))
    )
    (net (code "23") (name "INT_MI_03") (class "Default")
      (node (ref "J8") (pin "P$9") (pinfunction "P$9_P$9") (pintype "bidirectional"))
      (node (ref "U3") (pin "128") (pinfunction "P1_4_128") (pintype "bidirectional"))
    )
    (net (code "24") (name "INT_MI_04") (class "Default")
      (node (ref "J8") (pin "P$10") (pinfunction "P$10_P$10") (pintype "bidirectional"))
      (node (ref "U3") (pin "127") (pinfunction "P1_5_127") (pintype "bidirectional"))
    )
    (net (code "25") (name "LED1{slash}SPEED") (class "Default")
      (node (ref "RJ1") (pin "11") (pinfunction "YLO_11") (pintype "bidirectional"))
      (node (ref "U1") (pin "23") (pinfunction "LED0/ANEN_SPEED_23") (pintype "bidirectional"))
    )
    (net (code "26") (name "NC") (class "Default")
      (node (ref "RJ1") (pin "7") (pinfunction "P7_7") (pintype "bidirectional"))
    )
    (net (code "27") (name "Net-(C8-1)") (class "Default")
      (node (ref "C8") (pin "P$1") (pinfunction "1_P$1") (pintype "passive"))
      (node (ref "C9") (pin "P$1") (pinfunction "1_P$1") (pintype "passive"))
      (node (ref "FB1") (pin "2") (pinfunction "P$2_2") (pintype "bidirectional"))
      (node (ref "U1") (pin "2") (pinfunction "VDDA_3.3_2") (pintype "power_in"))
    )
    (net (code "28") (name "Net-(C24-2)") (class "Default")
      (node (ref "C24") (pin "P$2") (pinfunction "2_P$2") (pintype "passive"))
      (node (ref "U3") (pin "148") (pinfunction "VCL2_148") (pintype "bidirectional"))
    )
    (net (code "29") (name "Net-(C28-1)") (class "Default")
      (node (ref "C28") (pin "P$1") (pinfunction "1_P$1") (pintype "passive"))
      (node (ref "J7") (pin "P$1") (pinfunction "VBUS_P$1") (pintype "bidirectional"))
      (node (ref "R16") (pin "P$2") (pinfunction "2_P$2") (pintype "passive"))
      (node (ref "R21") (pin "P$2") (pinfunction "2_P$2") (pintype "passive"))
    )
    (net (code "30") (name "Net-(C33-1)") (class "Default")
      (node (ref "C33") (pin "P$1") (pinfunction "1_P$1") (pintype "passive"))
      (node (ref "U3") (pin "19") (pinfunction "VCLO_19") (pintype "bidirectional"))
    )
    (net (code "31") (name "Net-(C42-1)") (class "Default")
      (node (ref "C42") (pin "P$1") (pinfunction "1_P$1") (pintype "passive"))
      (node (ref "U3") (pin "62") (pinfunction "VCL1_62") (pintype "bidirectional"))
    )
    (net (code "32") (name "Net-(J7-D+)") (class "Default")
      (node (ref "J7") (pin "P$3") (pinfunction "D+_P$3") (pintype "bidirectional"))
      (node (ref "R18") (pin "P$2") (pinfunction "2_P$2") (pintype "passive"))
    )
    (net (code "33") (name "Net-(J7-D-)") (class "Default")
      (node (ref "J7") (pin "P$2") (pinfunction "D-_P$2") (pintype "bidirectional"))
      (node (ref "R17") (pin "P$2") (pinfunction "2_P$2") (pintype "passive"))
    )
    (net (code "34") (name "Net-(LED1-A)") (class "Default")
      (node (ref "LED1") (pin "1") (pinfunction "A_1") (pintype "passive"))
      (node (ref "R5") (pin "P$1") (pinfunction "1_P$1") (pintype "passive"))
    )
    (net (code "35") (name "Net-(R22-2)") (class "Default")
      (node (ref "R22") (pin "P$2") (pinfunction "2_P$2") (pintype "passive"))
      (node (ref "U3") (pin "27") (pinfunction "USBHS_RREF_27") (pintype "bidirectional"))
    )
    (net (code "36") (name "Net-(R23-2)") (class "Default")
      (node (ref "R23") (pin "P$2") (pinfunction "2_P$2") (pintype "passive"))
      (node (ref "U3") (pin "64") (pinfunction "VLO1(DCDC)_64") (pintype "bidirectional"))
    )
    (net (code "37") (name "Net-(R24-2)") (class "Default")
      (node (ref "R24") (pin "P$2") (pinfunction "2_P$2") (pintype "passive"))
      (node (ref "U3") (pin "65") (pinfunction "VLO2(DCDC)_65") (pintype "bidirectional"))
    )
    (net (code "38") (name "P0_00") (class "Default")
      (node (ref "J4") (pin "P$2") (pinfunction "P$2_P$2") (pintype "bidirectional"))
      (node (ref "U3") (pin "169") (pinfunction "P0_0/AN0\\00_169") (pintype "bidirectional"))
    )
    (net (code "39") (name "P0_01") (class "Default")
      (node (ref "J4") (pin "P$1") (pinfunction "P$1_P$1") (pintype "bidirectional"))
      (node (ref "U3") (pin "168") (pinfunction "P0_1/AN001_168") (pintype "bidirectional"))
    )
    (net (code "40") (name "P0_02") (class "Default")
      (node (ref "J5") (pin "1") (pinfunction "1_1") (pintype "passive"))
      (node (ref "U3") (pin "167") (pinfunction "P0_2/AN002_167") (pintype "bidirectional"))
    )
    (net (code "41") (name "P0_03") (class "Default")
      (node (ref "J5") (pin "3") (pinfunction "3_3") (pintype "passive"))
      (node (ref "U3") (pin "166") (pinfunction "P0_3/PGAVSS000_166") (pintype "bidirectional"))
    )
    (net (code "42") (name "P0_04") (class "Default")
      (node (ref "J5") (pin "5") (pinfunction "5_5") (pintype "passive"))
      (node (ref "U3") (pin "165") (pinfunction "P0_4/AN100_165") (pintype "bidirectional"))
    )
    (net (code "43") (name "P0_05") (class "Default")
      (node (ref "J5") (pin "7") (pinfunction "7_7") (pintype "passive"))
      (node (ref "U3") (pin "164") (pinfunction "P0_5/AN101_164") (pintype "bidirectional"))
    )
    (net (code "44") (name "P0_06") (class "Default")
      (node (ref "J5") (pin "9") (pinfunction "9_9") (pintype "passive"))
      (node (ref "U3") (pin "163") (pinfunction "P0_6/AN102_163") (pintype "bidirectional"))
    )
    (net (code "45") (name "P0_07") (class "Default")
      (node (ref "J5") (pin "10") (pinfunction "10_10") (pintype "passive"))
      (node (ref "U3") (pin "162") (pinfunction "P0_7/PGVSS100_162") (pintype "bidirectional"))
    )
    (net (code "46") (name "P0_08") (class "Default")
      (node (ref "J5") (pin "8") (pinfunction "8_8") (pintype "passive"))
      (node (ref "U3") (pin "161") (pinfunction "P0_8/AN003_161") (pintype "bidirectional"))
    )
    (net (code "47") (name "P0_09") (class "Default")
      (node (ref "J5") (pin "6") (pinfunction "6_6") (pintype "passive"))
      (node (ref "U3") (pin "160") (pinfunction "P0_9/AN004_160") (pintype "bidirectional"))
    )
    (net (code "48") (name "P0_14") (class "Default")
      (node (ref "J5") (pin "4") (pinfunction "4_4") (pintype "passive"))
      (node (ref "U3") (pin "152") (pinfunction "P0_14/DA0/AN005/AN105_152") (pintype "bidirectional"))
    )
    (net (code "49") (name "P0_15") (class "Default")
      (node (ref "J5") (pin "2") (pinfunction "2_2") (pintype "passive"))
      (node (ref "U3") (pin "151") (pinfunction "P0_15/DA1/AN006/AN106_151") (pintype "bidirectional"))
    )
    (net (code "50") (name "P1_02") (class "Default")
      (node (ref "J8") (pin "P$7") (pinfunction "P$7_P$7") (pintype "bidirectional"))
      (node (ref "U3") (pin "130") (pinfunction "P1_2_130") (pintype "bidirectional"))
    )
    (net (code "51") (name "P1_03") (class "Default")
      (node (ref "J8") (pin "P$8") (pinfunction "P$8_P$8") (pintype "bidirectional"))
      (node (ref "U3") (pin "129") (pinfunction "P1_3_129") (pintype "bidirectional"))
    )
    (net (code "52") (name "P1_06") (class "Default")
      (node (ref "J8") (pin "P$11") (pinfunction "P$11_P$11") (pintype "bidirectional"))
      (node (ref "U3") (pin "126") (pinfunction "P1_6_126") (pintype "bidirectional"))
    )
    (net (code "53") (name "P1_07") (class "Default")
      (node (ref "J8") (pin "P$12") (pinfunction "P$12_P$12") (pintype "bidirectional"))
      (node (ref "U3") (pin "125") (pinfunction "P1_7_125") (pintype "bidirectional"))
    )
    (net (code "54") (name "P1_11") (class "Default")
      (node (ref "J8") (pin "P$38") (pinfunction "P$38_P$38") (pintype "bidirectional"))
      (node (ref "U3") (pin "92") (pinfunction "P1_11_92") (pintype "bidirectional"))
    )
    (net (code "55") (name "P1_12") (class "Default")
      (node (ref "J8") (pin "P$37") (pinfunction "P$37_P$37") (pintype "bidirectional"))
      (node (ref "U3") (pin "93") (pinfunction "P1_12_93") (pintype "bidirectional"))
    )
    (net (code "56") (name "P1_13") (class "Default")
      (node (ref "J8") (pin "P$36") (pinfunction "P$36_P$36") (pintype "bidirectional"))
      (node (ref "U3") (pin "94") (pinfunction "P1_13_94") (pintype "bidirectional"))
    )
    (net (code "57") (name "P1_14") (class "Default")
      (node (ref "J8") (pin "P$35") (pinfunction "P$35_P$35") (pintype "bidirectional"))
      (node (ref "U3") (pin "95") (pinfunction "P1_14_95") (pintype "bidirectional"))
    )
    (net (code "58") (name "P1_15") (class "Default")
      (node (ref "J8") (pin "P$34") (pinfunction "P$34_P$34") (pintype "bidirectional"))
      (node (ref "U3") (pin "96") (pinfunction "P1_15_96") (pintype "bidirectional"))
    )
    (net (code "59") (name "P2_00") (class "Default")
      (node (ref "J10") (pin "P$13") (pinfunction "P$13_P$13") (pintype "bidirectional"))
      (node (ref "U3") (pin "69") (pinfunction "P2_0(INPUT_ONLY)_69") (pintype "bidirectional"))
    )
    (net (code "60") (name "P2_01") (class "Default")
      (node (ref "J10") (pin "P$14") (pinfunction "P$14_P$14") (pintype "bidirectional"))
      (node (ref "U3") (pin "68") (pinfunction "P2_1/MD_68") (pintype "bidirectional"))
    )
    (net (code "61") (name "P2_02") (class "Default")
      (node (ref "J4") (pin "P$9") (pinfunction "P$9_P$9") (pintype "bidirectional"))
      (node (ref "U3") (pin "54") (pinfunction "P2_2_54") (pintype "bidirectional"))
    )
    (net (code "62") (name "P2_03") (class "Default")
      (node (ref "J9") (pin "1") (pinfunction "1_1") (pintype "passive"))
      (node (ref "U3") (pin "53") (pinfunction "P2_3_53") (pintype "bidirectional"))
    )
    (net (code "63") (name "P2_04") (class "Default")
      (node (ref "J9") (pin "3") (pinfunction "3_3") (pintype "passive"))
      (node (ref "U3") (pin "52") (pinfunction "P2_4_52") (pintype "bidirectional"))
    )
    (net (code "64") (name "P2_05") (class "Default")
      (node (ref "J9") (pin "5") (pinfunction "5_5") (pintype "passive"))
      (node (ref "U3") (pin "51") (pinfunction "P2_5_51") (pintype "bidirectional"))
    )
    (net (code "65") (name "P2_06") (class "Default")
      (node (ref "J9") (pin "7") (pinfunction "7_7") (pintype "passive"))
      (node (ref "U3") (pin "50") (pinfunction "P2_6_50") (pintype "bidirectional"))
    )
    (net (code "66") (name "P2_07") (class "Default")
      (node (ref "J9") (pin "9") (pinfunction "9_9") (pintype "passive"))
      (node (ref "U3") (pin "49") (pinfunction "P2_7_49") (pintype "bidirectional"))
    )
    (net (code "67") (name "P3_03") (class "Default")
      (node (ref "J10") (pin "P$2") (pinfunction "P$2_P$2") (pintype "bidirectional"))
      (node (ref "U3") (pin "85") (pinfunction "P3_3_85") (pintype "bidirectional"))
    )
    (net (code "68") (name "P3_04") (class "Default")
      (node (ref "J10") (pin "P$4") (pinfunction "P$4_P$4") (pintype "bidirectional"))
      (node (ref "U3") (pin "82") (pinfunction "P3_4_82") (pintype "bidirectional"))
    )
    (net (code "69") (name "P3_05") (class "Default")
      (node (ref "J10") (pin "P$6") (pinfunction "P$6_P$6") (pintype "bidirectional"))
      (node (ref "U3") (pin "81") (pinfunction "P3_5_81") (pintype "bidirectional"))
    )
    (net (code "70") (name "P3_06") (class "Default")
      (node (ref "J10") (pin "P$1") (pinfunction "P$1_P$1") (pintype "bidirectional"))
      (node (ref "U3") (pin "80") (pinfunction "P3_6_80") (pintype "bidirectional"))
    )
    (net (code "71") (name "P3_07") (class "Default")
      (node (ref "J10") (pin "P$3") (pinfunction "P$3_P$3") (pintype "bidirectional"))
      (node (ref "U3") (pin "79") (pinfunction "P3_7_79") (pintype "bidirectional"))
    )
    (net (code "72") (name "P3_09") (class "Default")
      (node (ref "J10") (pin "P$5") (pinfunction "P$5_P$5") (pintype "bidirectional"))
      (node (ref "U3") (pin "77") (pinfunction "P3_9_77") (pintype "bidirectional"))
    )
    (net (code "73") (name "P3_10") (class "Default")
      (node (ref "J10") (pin "P$7") (pinfunction "P$7_P$7") (pintype "bidirectional"))
      (node (ref "U3") (pin "76") (pinfunction "P3_10_76") (pintype "bidirectional"))
    )
    (net (code "74") (name "P3_11") (class "Default")
      (node (ref "J10") (pin "P$8") (pinfunction "P$8_P$8") (pintype "bidirectional"))
      (node (ref "U3") (pin "75") (pinfunction "P3_11_75") (pintype "bidirectional"))
    )
    (net (code "75") (name "P3_12") (class "Default")
      (node (ref "J10") (pin "P$9") (pinfunction "P$9_P$9") (pintype "bidirectional"))
      (node (ref "U3") (pin "74") (pinfunction "P3_12_74") (pintype "bidirectional"))
    )
    (net (code "76") (name "P3_13") (class "Default")
      (node (ref "J10") (pin "P$20") (pinfunction "P$20_P$20") (pintype "bidirectional"))
      (node (ref "U3") (pin "55") (pinfunction "P3_13_55") (pintype "bidirectional"))
    )
    (net (code "77") (name "P3_14") (class "Default")
      (node (ref "J10") (pin "P$17") (pinfunction "P$17_P$17") (pintype "bidirectional"))
      (node (ref "U3") (pin "56") (pinfunction "P3_14_56") (pintype "bidirectional"))
    )
    (net (code "78") (name "P3_15") (class "Default")
      (node (ref "J10") (pin "P$18") (pinfunction "P$18_P$18") (pintype "bidirectional"))
      (node (ref "U3") (pin "57") (pinfunction "P3_15_57") (pintype "bidirectional"))
    )
    (net (code "79") (name "P4_00") (class "Default")
      (node (ref "J4") (pin "P$7") (pinfunction "P$7_P$7") (pintype "bidirectional"))
      (node (ref "U3") (pin "1") (pinfunction "P4_0_1") (pintype "bidirectional"))
    )
    (net (code "80") (name "P4_01") (class "Default")
      (node (ref "J4") (pin "P$8") (pinfunction "P$8_P$8") (pintype "bidirectional"))
      (node (ref "U3") (pin "2") (pinfunction "P4_1_2") (pintype "bidirectional"))
    )
    (net (code "81") (name "P4_02") (class "Default")
      (node (ref "U3") (pin "3") (pinfunction "P4_2_3") (pintype "bidirectional"))
    )
    (net (code "82") (name "P4_08") (class "Default")
      (node (ref "J4") (pin "P$20") (pinfunction "P$20_P$20") (pintype "bidirectional"))
      (node (ref "U3") (pin "43") (pinfunction "P4_8_43") (pintype "bidirectional"))
    )
    (net (code "83") (name "P4_09") (class "Default")
      (node (ref "J4") (pin "P$19") (pinfunction "P$19_P$19") (pintype "bidirectional"))
      (node (ref "U3") (pin "42") (pinfunction "P4_9_42") (pintype "bidirectional"))
    )
    (net (code "84") (name "P4_10") (class "Default")
      (node (ref "J4") (pin "P$18") (pinfunction "P$18_P$18") (pintype "bidirectional"))
      (node (ref "U3") (pin "41") (pinfunction "P4_10_41") (pintype "bidirectional"))
    )
    (net (code "85") (name "P4_11") (class "Default")
      (node (ref "J4") (pin "P$17") (pinfunction "P$17_P$17") (pintype "bidirectional"))
      (node (ref "U3") (pin "40") (pinfunction "P4_11_40") (pintype "bidirectional"))
    )
    (net (code "86") (name "P4_12") (class "Default")
      (node (ref "J4") (pin "P$16") (pinfunction "P$16_P$16") (pintype "bidirectional"))
      (node (ref "U3") (pin "39") (pinfunction "P4_12_39") (pintype "bidirectional"))
    )
    (net (code "87") (name "P4_13") (class "Default")
      (node (ref "J4") (pin "P$15") (pinfunction "P$15_P$15") (pintype "bidirectional"))
      (node (ref "U3") (pin "38") (pinfunction "P4_13_38") (pintype "bidirectional"))
    )
    (net (code "88") (name "P4_14") (class "Default")
      (node (ref "J4") (pin "P$14") (pinfunction "P$14_P$14") (pintype "bidirectional"))
      (node (ref "U3") (pin "37") (pinfunction "P4_14_37") (pintype "bidirectional"))
    )
    (net (code "89") (name "P4_15") (class "Default")
      (node (ref "J4") (pin "P$13") (pinfunction "P$13_P$13") (pintype "bidirectional"))
      (node (ref "U3") (pin "36") (pinfunction "P4_15_36") (pintype "bidirectional"))
    )
    (net (code "90") (name "P5_11") (class "Default")
      (node (ref "J4") (pin "P$6") (pinfunction "P$6_P$6") (pintype "bidirectional"))
      (node (ref "U3") (pin "176") (pinfunction "P5_11_176") (pintype "bidirectional"))
    )
    (net (code "91") (name "P5_12") (class "Default")
      (node (ref "J4") (pin "P$5") (pinfunction "P$5_P$5") (pintype "bidirectional"))
      (node (ref "U3") (pin "175") (pinfunction "P5_12_175") (pintype "bidirectional"))
    )
    (net (code "92") (name "P5_13") (class "Default")
      (node (ref "J4") (pin "P$4") (pinfunction "P$4_P$4") (pintype "bidirectional"))
      (node (ref "U3") (pin "174") (pinfunction "P5_13_174") (pintype "bidirectional"))
    )
    (net (code "93") (name "P6_00") (class "Default")
      (node (ref "J8") (pin "P$13") (pinfunction "P$13_P$13") (pintype "bidirectional"))
      (node (ref "U3") (pin "122") (pinfunction "P6_0_122") (pintype "bidirectional"))
    )
    (net (code "94") (name "P6_01") (class "Default")
      (node (ref "J8") (pin "P$14") (pinfunction "P$14_P$14") (pintype "bidirectional"))
      (node (ref "U3") (pin "121") (pinfunction "P6_1_121") (pintype "bidirectional"))
    )
    (net (code "95") (name "P6_02") (class "Default")
      (node (ref "J8") (pin "P$15") (pinfunction "P$15_P$15") (pintype "bidirectional"))
      (node (ref "U3") (pin "120") (pinfunction "P6_2_120") (pintype "bidirectional"))
    )
    (net (code "96") (name "P6_03") (class "Default")
      (node (ref "J8") (pin "P$16") (pinfunction "P$16_P$16") (pintype "bidirectional"))
      (node (ref "U3") (pin "119") (pinfunction "P6_3_119") (pintype "bidirectional"))
    )
    (net (code "97") (name "P6_04") (class "Default")
      (node (ref "J8") (pin "P$17") (pinfunction "P$17_P$17") (pintype "bidirectional"))
      (node (ref "U3") (pin "118") (pinfunction "P6_4_118") (pintype "bidirectional"))
    )
    (net (code "98") (name "P6_05") (class "Default")
      (node (ref "J8") (pin "P$18") (pinfunction "P$18_P$18") (pintype "bidirectional"))
      (node (ref "U3") (pin "117") (pinfunction "P6_5_117") (pintype "bidirectional"))
    )
    (net (code "99") (name "P6_06") (class "Default")
      (node (ref "J8") (pin "P$19") (pinfunction "P$19_P$19") (pintype "bidirectional"))
      (node (ref "U3") (pin "116") (pinfunction "P6_6_116") (pintype "bidirectional"))
    )
    (net (code "100") (name "P6_07") (class "Default")
      (node (ref "J8") (pin "P$20") (pinfunction "P$20_P$20") (pintype "bidirectional"))
      (node (ref "U3") (pin "115") (pinfunction "P6_7_115") (pintype "bidirectional"))
    )
    (net (code "101") (name "P6_08") (class "Default")
      (node (ref "J8") (pin "P$33") (pinfunction "P$33_P$33") (pintype "bidirectional"))
      (node (ref "U3") (pin "99") (pinfunction "P6_8_99") (pintype "bidirectional"))
    )
    (net (code "102") (name "P6_09") (class "Default")
      (node (ref "J8") (pin "P$32") (pinfunction "P$32_P$32") (pintype "bidirectional"))
      (node (ref "U3") (pin "100") (pinfunction "P6_9_100") (pintype "bidirectional"))
    )
    (net (code "103") (name "P6_10") (class "Default")
      (node (ref "J8") (pin "P$31") (pinfunction "P$31_P$31") (pintype "bidirectional"))
      (node (ref "U3") (pin "101") (pinfunction "P6_10_101") (pintype "bidirectional"))
    )
    (net (code "104") (name "P6_11") (class "Default")
      (node (ref "J8") (pin "P$30") (pinfunction "P$30_P$30") (pintype "bidirectional"))
      (node (ref "U3") (pin "102") (pinfunction "P6_11_102") (pintype "bidirectional"))
    )
    (net (code "105") (name "P6_12") (class "Default")
      (node (ref "J8") (pin "P$29") (pinfunction "P$29_P$29") (pintype "bidirectional"))
      (node (ref "U3") (pin "103") (pinfunction "P6_12_103") (pintype "bidirectional"))
    )
    (net (code "106") (name "P6_13") (class "Default")
      (node (ref "J8") (pin "P$28") (pinfunction "P$28_P$28") (pintype "bidirectional"))
      (node (ref "U3") (pin "104") (pinfunction "P6_13_104") (pintype "bidirectional"))
    )
    (net (code "107") (name "P6_14") (class "Default")
      (node (ref "J8") (pin "P$27") (pinfunction "P$27_P$27") (pintype "bidirectional"))
      (node (ref "U3") (pin "105") (pinfunction "P6_14_105") (pintype "bidirectional"))
    )
    (net (code "108") (name "P6_15") (class "Default")
      (node (ref "J8") (pin "P$26") (pinfunction "P$26_P$26") (pintype "bidirectional"))
      (node (ref "U3") (pin "106") (pinfunction "P6_15_106") (pintype "bidirectional"))
    )
    (net (code "109") (name "P7_06") (class "Default")
      (node (ref "J4") (pin "P$10") (pinfunction "P$10_P$10") (pintype "bidirectional"))
      (node (ref "U3") (pin "14") (pinfunction "P7_6_14") (pintype "bidirectional"))
    )
    (net (code "110") (name "P7_07") (class "Default")
      (node (ref "J4") (pin "P$11") (pinfunction "P$11_P$11") (pintype "bidirectional"))
      (node (ref "U3") (pin "15") (pinfunction "P7_7_15") (pintype "bidirectional"))
    )
    (net (code "111") (name "P8_00") (class "Default")
      (node (ref "J8") (pin "P$4") (pinfunction "P$4_P$4") (pintype "bidirectional"))
      (node (ref "U3") (pin "133") (pinfunction "P8_0_133") (pintype "bidirectional"))
    )
    (net (code "112") (name "P8_01") (class "Default")
      (node (ref "J8") (pin "P$3") (pinfunction "P$3_P$3") (pintype "bidirectional"))
      (node (ref "U3") (pin "134") (pinfunction "P8_1_134") (pintype "bidirectional"))
    )
    (net (code "113") (name "P8_02") (class "Default")
      (node (ref "J8") (pin "P$2") (pinfunction "P$2_P$2") (pintype "bidirectional"))
      (node (ref "U3") (pin "135") (pinfunction "P8_2_135") (pintype "bidirectional"))
    )
    (net (code "114") (name "P8_03") (class "Default")
      (node (ref "U3") (pin "136") (pinfunction "P8_3_136") (pintype "bidirectional"))
    )
    (net (code "115") (name "P8_04") (class "Default")
      (node (ref "U3") (pin "137") (pinfunction "P8_4_137") (pintype "bidirectional"))
    )
    (net (code "116") (name "P8_05") (class "Default")
      (node (ref "J4") (pin "P$3") (pinfunction "P$3_P$3") (pintype "bidirectional"))
      (node (ref "U3") (pin "173") (pinfunction "P8_5_173") (pintype "bidirectional"))
    )
    (net (code "117") (name "P9_00") (class "Default")
      (node (ref "J10") (pin "P$16") (pinfunction "P$16_P$16") (pintype "bidirectional"))
      (node (ref "U3") (pin "58") (pinfunction "P9_0_58") (pintype "bidirectional"))
    )
    (net (code "118") (name "P9_01") (class "Default")
      (node (ref "J10") (pin "P$15") (pinfunction "P$15_P$15") (pintype "bidirectional"))
      (node (ref "U3") (pin "59") (pinfunction "P9_1_59") (pintype "bidirectional"))
    )
    (net (code "119") (name "P9_05") (class "Default")
      (node (ref "J10") (pin "P$10") (pinfunction "P$10_P$10") (pintype "bidirectional"))
      (node (ref "U3") (pin "73") (pinfunction "P9_5_73") (pintype "bidirectional"))
    )
    (net (code "120") (name "P9_06") (class "Default")
      (node (ref "J10") (pin "P$11") (pinfunction "P$11_P$11") (pintype "bidirectional"))
      (node (ref "U3") (pin "72") (pinfunction "P9_6_72") (pintype "bidirectional"))
    )
    (net (code "121") (name "P9_07") (class "Default")
      (node (ref "J10") (pin "P$12") (pinfunction "P$12_P$12") (pintype "bidirectional"))
      (node (ref "U3") (pin "71") (pinfunction "P9_7_71") (pintype "bidirectional"))
    )
    (net (code "122") (name "P9_08") (class "Default")
      (node (ref "U3") (pin "70") (pinfunction "P9_8_70") (pintype "bidirectional"))
    )
    (net (code "123") (name "PA_00") (class "Default")
      (node (ref "J8") (pin "P$21") (pinfunction "P$21_P$21") (pintype "bidirectional"))
      (node (ref "U3") (pin "114") (pinfunction "PA_0_114") (pintype "bidirectional"))
    )
    (net (code "124") (name "PA_01") (class "Default")
      (node (ref "J8") (pin "P$22") (pinfunction "P$22_P$22") (pintype "bidirectional"))
      (node (ref "U3") (pin "113") (pinfunction "PA_1_113") (pintype "bidirectional"))
    )
    (net (code "125") (name "PA_08") (class "Default")
      (node (ref "J8") (pin "P$25") (pinfunction "P$25_P$25") (pintype "bidirectional"))
      (node (ref "U3") (pin "107") (pinfunction "PA_8_107") (pintype "bidirectional"))
    )
    (net (code "126") (name "PA_09") (class "Default")
      (node (ref "J8") (pin "P$24") (pinfunction "P$24_P$24") (pintype "bidirectional"))
      (node (ref "U3") (pin "108") (pinfunction "PA_9_108") (pintype "bidirectional"))
    )
    (net (code "127") (name "PA_10") (class "Default")
      (node (ref "J8") (pin "P$23") (pinfunction "P$23_P$23") (pintype "bidirectional"))
      (node (ref "U3") (pin "109") (pinfunction "PA_10_109") (pintype "bidirectional"))
    )
    (net (code "128") (name "PB_00") (class "Default")
      (node (ref "J4") (pin "P$12") (pinfunction "P$12_P$12") (pintype "bidirectional"))
      (node (ref "U3") (pin "16") (pinfunction "PB_0_16") (pintype "bidirectional"))
    )
    (net (code "129") (name "R51") (class "Default")
      (node (ref "R7") (pin "P$1") (pinfunction "1_P$1") (pintype "passive"))
      (node (ref "RJ1") (pin "12") (pinfunction "YHI_12") (pintype "bidirectional"))
    )
    (net (code "130") (name "R52") (class "Default")
      (node (ref "R8") (pin "P$1") (pinfunction "1_P$1") (pintype "passive"))
      (node (ref "RJ1") (pin "9") (pinfunction "GHI_9") (pintype "bidirectional"))
    )
    (net (code "131") (name "RESET") (class "Default")
      (node (ref "C16") (pin "P$1") (pinfunction "1_P$1") (pintype "passive"))
      (node (ref "J3") (pin "9") (pinfunction "9_9") (pintype "passive"))
      (node (ref "R13") (pin "P$1") (pinfunction "1_P$1") (pintype "passive"))
      (node (ref "U3") (pin "67") (pinfunction "RES#_67") (pintype "bidirectional"))
    )
    (net (code "132") (name "REXT") (class "Default")
      (node (ref "C3") (pin "P$1") (pinfunction "1_P$1") (pintype "passive"))
      (node (ref "R1") (pin "P$2") (pinfunction "2_P$2") (pintype "passive"))
      (node (ref "U1") (pin "9") (pinfunction "REXT_9") (pintype "input"))
    )
    (net (code "133") (name "RXD0") (class "Default")
      (node (ref "R10") (pin "P$2") (pinfunction "2_P$2") (pintype "passive"))
      (node (ref "U1") (pin "13") (pinfunction "RXD0_13") (pintype "bidirectional"))
    )
    (net (code "134") (name "RXD1") (class "Default")
      (node (ref "R9") (pin "P$2") (pinfunction "2_P$2") (pintype "passive"))
      (node (ref "U1") (pin "12") (pinfunction "RXD1_12") (pintype "bidirectional"))
    )
    (net (code "135") (name "RXER") (class "Default")
      (node (ref "R11") (pin "P$2") (pinfunction "2_P$2") (pintype "passive"))
      (node (ref "U1") (pin "17") (pinfunction "RXER_17") (pintype "bidirectional"))
    )
    (net (code "136") (name "RXM") (class "Default")
      (node (ref "RJ1") (pin "6") (pinfunction "RD-_6") (pintype "bidirectional"))
      (node (ref "U1") (pin "3") (pinfunction "RXM_3") (pintype "bidirectional"))
    )
    (net (code "137") (name "RXP") (class "Default")
      (node (ref "RJ1") (pin "3") (pinfunction "RD+_3") (pintype "bidirectional"))
      (node (ref "U1") (pin "4") (pinfunction "RXP_4") (pintype "bidirectional"))
    )
    (net (code "138") (name "SD1_CD") (class "Default")
      (node (ref "J1") (pin "10") (pinfunction "CD_SWITCH2_10") (pintype "bidirectional"))
      (node (ref "U3") (pin "146") (pinfunction "P5_6/AN019_146") (pintype "bidirectional"))
    )
    (net (code "139") (name "SD1_CLK") (class "Default")
      (node (ref "J1") (pin "5") (pinfunction "CLOCK_5") (pintype "bidirectional"))
      (node (ref "U3") (pin "140") (pinfunction "P5_0/AN016_140") (pintype "bidirectional"))
    )
    (net (code "140") (name "SD1_CMD") (class "Default")
      (node (ref "J1") (pin "3") (pinfunction "COMMAND/RESPONSE_3") (pintype "bidirectional"))
      (node (ref "U3") (pin "141") (pinfunction "P5_1/AN116_141") (pintype "bidirectional"))
    )
    (net (code "141") (name "SD1_DAT0") (class "Default")
      (node (ref "J1") (pin "7") (pinfunction "DATA_LINE[BIT_0]_7") (pintype "bidirectional"))
      (node (ref "U3") (pin "142") (pinfunction "P5_2/AN017_142") (pintype "bidirectional"))
    )
    (net (code "142") (name "SD1_DAT1") (class "Default")
      (node (ref "J1") (pin "8") (pinfunction "DATA_LINE[BIT_1]_8") (pintype "bidirectional"))
      (node (ref "U3") (pin "143") (pinfunction "P5_3/AN117_143") (pintype "bidirectional"))
    )
    (net (code "143") (name "SD1_DAT2") (class "Default")
      (node (ref "J1") (pin "1") (pinfunction "DATA_LINE[BIT_2]_1") (pintype "bidirectional"))
      (node (ref "U3") (pin "144") (pinfunction "P5_4/AN018_144") (pintype "bidirectional"))
    )
    (net (code "144") (name "SD1_DAT3") (class "Default")
      (node (ref "J1") (pin "2") (pinfunction "CARD_DETECT/DATA_LINE[BIT_3]_2") (pintype "bidirectional"))
      (node (ref "U3") (pin "145") (pinfunction "P5_5/AN118_145") (pintype "bidirectional"))
    )
    (net (code "145") (name "SD1_WP") (class "Default")
      (node (ref "J1") (pin "9") (pinfunction "CD_SWITCH1_9") (pintype "bidirectional"))
      (node (ref "U3") (pin "147") (pinfunction "P5_7/AN119_147") (pintype "bidirectional"))
    )
    (net (code "146") (name "TCK") (class "Default")
      (node (ref "J3") (pin "7") (pinfunction "7_7") (pintype "passive"))
      (node (ref "U3") (pin "88") (pinfunction "P3_0_88") (pintype "bidirectional"))
    )
    (net (code "147") (name "TDI") (class "Default")
      (node (ref "J3") (pin "1") (pinfunction "1_1") (pintype "passive"))
      (node (ref "U3") (pin "91") (pinfunction "P1_10_91") (pintype "bidirectional"))
    )
    (net (code "148") (name "TDO") (class "Default")
      (node (ref "J3") (pin "3") (pinfunction "3_3") (pintype "passive"))
      (node (ref "U3") (pin "90") (pinfunction "P1_9_90") (pintype "bidirectional"))
    )
    (net (code "149") (name "TMS") (class "Default")
      (node (ref "J3") (pin "5") (pinfunction "5_5") (pintype "passive"))
      (node (ref "U3") (pin "89") (pinfunction "P1_8_89") (pintype "bidirectional"))
    )
    (net (code "150") (name "TXM") (class "Default")
      (node (ref "RJ1") (pin "2") (pinfunction "TD-_2") (pintype "bidirectional"))
      (node (ref "U1") (pin "5") (pinfunction "TXM_5") (pintype "bidirectional"))
    )
    (net (code "151") (name "TXP") (class "Default")
      (node (ref "RJ1") (pin "1") (pinfunction "TD+_1") (pintype "bidirectional"))
      (node (ref "U1") (pin "6") (pinfunction "TXP_6") (pintype "bidirectional"))
    )
    (net (code "152") (name "USBHS_FAULT") (class "Default")
      (node (ref "R19") (pin "P$1") (pinfunction "1_P$1") (pintype "passive"))
      (node (ref "U2") (pin "3") (pinfunction "FLG_3") (pintype "input"))
      (node (ref "U3") (pin "78") (pinfunction "P3_8_78") (pintype "bidirectional"))
    )
    (net (code "153") (name "USBHS_N") (class "Default")
      (node (ref "J6") (pin "D-") (pinfunction "D-_D-") (pintype "bidirectional"))
      (node (ref "U3") (pin "31") (pinfunction "USBHS_DM_31") (pintype "bidirectional"))
    )
    (net (code "154") (name "USBHS_P") (class "Default")
      (node (ref "J6") (pin "D+") (pinfunction "D+_D+") (pintype "bidirectional"))
      (node (ref "U3") (pin "32") (pinfunction "USBHS_DP_32") (pintype "bidirectional"))
    )
    (net (code "155") (name "USBHS_VBUS") (class "Default")
      (node (ref "C29") (pin "P$1") (pinfunction "1_P$1") (pintype "passive"))
      (node (ref "C31") (pin "1") (pinfunction "1_1") (pintype "passive"))
      (node (ref "J6") (pin "VBUS") (pinfunction "VBUS_VBUS") (pintype "power_in"))
      (node (ref "U2") (pin "5") (pinfunction "OUT_5") (pintype "input"))
      (node (ref "U3") (pin "17") (pinfunction "PB_1_17") (pintype "bidirectional"))
    )
    (net (code "156") (name "USBHS_VBUSEN") (class "Default")
      (node (ref "R20") (pin "P$1") (pinfunction "1_P$1") (pintype "passive"))
      (node (ref "U2") (pin "1") (pinfunction "EN_1") (pintype "input"))
    )
    (net (code "157") (name "USB_N") (class "Default")
      (node (ref "R17") (pin "P$1") (pinfunction "1_P$1") (pintype "passive"))
      (node (ref "U3") (pin "46") (pinfunction "USB_DM_46") (pintype "bidirectional"))
    )
    (net (code "158") (name "USB_P") (class "Default")
      (node (ref "R18") (pin "P$1") (pinfunction "1_P$1") (pintype "passive"))
      (node (ref "U3") (pin "47") (pinfunction "USB_DP_47") (pintype "bidirectional"))
    )
    (net (code "159") (name "USB_VBUS_B") (class "Default")
      (node (ref "R16") (pin "P$1") (pinfunction "1_P$1") (pintype "passive"))
      (node (ref "U3") (pin "44") (pinfunction "P4_7_44") (pintype "bidirectional"))
    )
    (net (code "160") (name "VCL_F(FLASH)") (class "Default")
      (node (ref "C34") (pin "P$2") (pinfunction "2_P$2") (pintype "passive"))
      (node (ref "U3") (pin "112") (pinfunction "VCL_F(FLASH)_112") (pintype "bidirectional"))
    )
    (net (code "161") (name "VDD") (class "Default")
      (node (ref "C14") (pin "P$1") (pinfunction "1_P$1") (pintype "passive"))
      (node (ref "C15") (pin "P$1") (pinfunction "1_P$1") (pintype "passive"))
      (node (ref "C19") (pin "P$2") (pinfunction "2_P$2") (pintype "passive"))
      (node (ref "C20") (pin "P$2") (pinfunction "2_P$2") (pintype "passive"))
      (node (ref "C21") (pin "P$2") (pinfunction "2_P$2") (pintype "passive"))
      (node (ref "C22") (pin "P$2") (pinfunction "2_P$2") (pintype "passive"))
      (node (ref "C25") (pin "P$2") (pinfunction "2_P$2") (pintype "passive"))
      (node (ref "C27") (pin "P$2") (pinfunction "2_P$2") (pintype "passive"))
      (node (ref "C30") (pin "P$2") (pinfunction "2_P$2") (pintype "passive"))
      (node (ref "C35") (pin "P$2") (pinfunction "2_P$2") (pintype "passive"))
      (node (ref "C36") (pin "P$1") (pinfunction "1_P$1") (pintype "passive"))
      (node (ref "C38") (pin "P$2") (pinfunction "2_P$2") (pintype "passive"))
      (node (ref "C39") (pin "P$1") (pinfunction "1_P$1") (pintype "passive"))
      (node (ref "C4") (pin "P$1") (pinfunction "1_P$1") (pintype "passive"))
      (node (ref "C40") (pin "P$1") (pinfunction "1_P$1") (pintype "passive"))
      (node (ref "C41") (pin "P$1") (pinfunction "1_P$1") (pintype "passive"))
      (node (ref "C43") (pin "P$2") (pinfunction "2_P$2") (pintype "passive"))
      (node (ref "C5") (pin "P$1") (pinfunction "1_P$1") (pintype "passive"))
      (node (ref "C7") (pin "P$1") (pinfunction "1_P$1") (pintype "passive"))
      (node (ref "FB1") (pin "1") (pinfunction "P$1_1") (pintype "bidirectional"))
      (node (ref "J1") (pin "4") (pinfunction "SUPPLY_VOLTAGE_4") (pintype "power_in"))
      (node (ref "J3") (pin "2") (pinfunction "2_2") (pintype "passive"))
      (node (ref "J3") (pin "4") (pinfunction "4_4") (pintype "passive"))
      (node (ref "L1") (pin "2") (pinfunction "P$2_2") (pintype "bidirectional"))
      (node (ref "R13") (pin "P$2") (pinfunction "2_P$2") (pintype "passive"))
      (node (ref "R14") (pin "P$1") (pinfunction "1_P$1") (pintype "passive"))
      (node (ref "R15") (pin "P$1") (pinfunction "1_P$1") (pintype "passive"))
      (node (ref "R2") (pin "P$2") (pinfunction "2_P$2") (pintype "passive"))
      (node (ref "R3") (pin "P$2") (pinfunction "2_P$2") (pintype "passive"))
      (node (ref "R4") (pin "P$2") (pinfunction "2_P$2") (pintype "passive"))
      (node (ref "R5") (pin "P$2") (pinfunction "2_P$2") (pintype "passive"))
      (node (ref "R6") (pin "P$2") (pinfunction "2_P$2") (pintype "passive"))
      (node (ref "R7") (pin "P$2") (pinfunction "2_P$2") (pintype "passive"))
      (node (ref "R8") (pin "P$2") (pinfunction "2_P$2") (pintype "passive"))
      (node (ref "U1") (pin "14") (pinfunction "VDDIO_14") (pintype "power_in"))
      (node (ref "U3") (pin "110") (pinfunction "VCC(IO)5_110") (pintype "bidirectional"))
      (node (ref "U3") (pin "123") (pinfunction "VCC(IO)6_123") (pintype "bidirectional"))
      (node (ref "U3") (pin "138") (pinfunction "VCC(IO)7_138") (pintype "bidirectional"))
      (node (ref "U3") (pin "149") (pinfunction "VCC(IO)8_149") (pintype "bidirectional"))
      (node (ref "U3") (pin "154") (pinfunction "VREFH_154") (pintype "bidirectional"))
      (node (ref "U3") (pin "155") (pinfunction "AVCC0_155") (pintype "bidirectional"))
      (node (ref "U3") (pin "158") (pinfunction "VREFH0_158") (pintype "bidirectional"))
      (node (ref "U3") (pin "171") (pinfunction "VCC(IO)9_171") (pintype "bidirectional"))
      (node (ref "U3") (pin "25") (pinfunction "VCC1_25") (pintype "bidirectional"))
      (node (ref "U3") (pin "26") (pinfunction "AVCC_SUBHS_26") (pintype "bidirectional"))
      (node (ref "U3") (pin "34") (pinfunction "VCC_USBHS_34") (pintype "bidirectional"))
      (node (ref "U3") (pin "48") (pinfunction "VCC_USB_48") (pintype "bidirectional"))
      (node (ref "U3") (pin "61") (pinfunction "VCC(IO)2_61") (pintype "bidirectional"))
      (node (ref "U3") (pin "84") (pinfunction "VCC(IO)3_84") (pintype "bidirectional"))
      (node (ref "U3") (pin "97") (pinfunction "VCC(IO)4_97") (pintype "bidirectional"))
    )
    (net (code "162") (name "VDD5") (class "Default")
      (node (ref "C23") (pin "P$1") (pinfunction "1_P$1") (pintype "passive"))
      (node (ref "C26") (pin "P$1") (pinfunction "1_P$1") (pintype "passive"))
      (node (ref "J2") (pin "P$3") (pinfunction "P$3_P$3") (pintype "bidirectional"))
      (node (ref "R19") (pin "P$2") (pinfunction "2_P$2") (pintype "passive"))
      (node (ref "R20") (pin "P$2") (pinfunction "2_P$2") (pintype "passive"))
      (node (ref "U2") (pin "4") (pinfunction "VIN_4") (pintype "input"))
    )
    (net (code "163") (name "VDDIN") (class "Default")
      (node (ref "J2") (pin "P$2") (pinfunction "P$2_P$2") (pintype "bidirectional"))
      (node (ref "L1") (pin "1") (pinfunction "P$1_1") (pintype "bidirectional"))
    )
    (net (code "164") (name "VDD_1.2") (class "Default")
      (node (ref "C10") (pin "P$1") (pinfunction "1_P$1") (pintype "passive"))
      (node (ref "C11") (pin "P$1") (pinfunction "1_P$1") (pintype "passive"))
      (node (ref "U1") (pin "1") (pinfunction "VDD_1.2_1") (pintype "power_in"))
    )
    (net (code "165") (name "XCIN") (class "Default")
      (node (ref "C32") (pin "P$1") (pinfunction "1_P$1") (pintype "passive"))
      (node (ref "U3") (pin "20") (pinfunction "XCIN_20") (pintype "bidirectional"))
      (node (ref "X3") (pin "P$1") (pinfunction "P$1_P$1") (pintype "bidirectional"))
    )
    (net (code "166") (name "XCOUT") (class "Default")
      (node (ref "C37") (pin "P$1") (pinfunction "1_P$1") (pintype "passive"))
      (node (ref "U3") (pin "21") (pinfunction "XCOUT_21") (pintype "bidirectional"))
      (node (ref "X3") (pin "P$2") (pinfunction "P$2_P$2") (pintype "bidirectional"))
    )
    (net (code "167") (name "XII") (class "Default")
      (node (ref "C1") (pin "P$1") (pinfunction "1_P$1") (pintype "passive"))
      (node (ref "U1") (pin "8") (pinfunction "XI_8") (pintype "input"))
      (node (ref "X1") (pin "1") (pinfunction "1_1") (pintype "bidirectional"))
    )
    (net (code "168") (name "XOO") (class "Default")
      (node (ref "C2") (pin "P$1") (pinfunction "1_P$1") (pintype "passive"))
      (node (ref "U1") (pin "7") (pinfunction "XO_7") (pintype "output"))
      (node (ref "X1") (pin "3") (pinfunction "3_3") (pintype "bidirectional"))
    )
    (net (code "169") (name "XTAL1") (class "Default")
      (node (ref "C17") (pin "P$1") (pinfunction "1_P$1") (pintype "passive"))
      (node (ref "U3") (pin "23") (pinfunction "P2_13/XTAL_23") (pintype "bidirectional"))
      (node (ref "X2") (pin "1") (pinfunction "1_1") (pintype "bidirectional"))
    )
    (net (code "170") (name "XTAL2") (class "Default")
      (node (ref "C18") (pin "P$1") (pinfunction "1_P$1") (pintype "passive"))
      (node (ref "U3") (pin "24") (pinfunction "P2_12/EXTAL_24") (pintype "bidirectional"))
      (node (ref "X2") (pin "3") (pinfunction "3_3") (pintype "bidirectional"))
    )
    (net (code "171") (name "unconnected-(U3-VBAT-Pad18)") (class "Default")
      (node (ref "U3") (pin "18") (pinfunction "VBAT_18") (pintype "bidirectional"))
    )
  )
)
